# TCU_UCU_PCB_Rev2.net
KiCad netlist of a schematic drawn in EAGLE
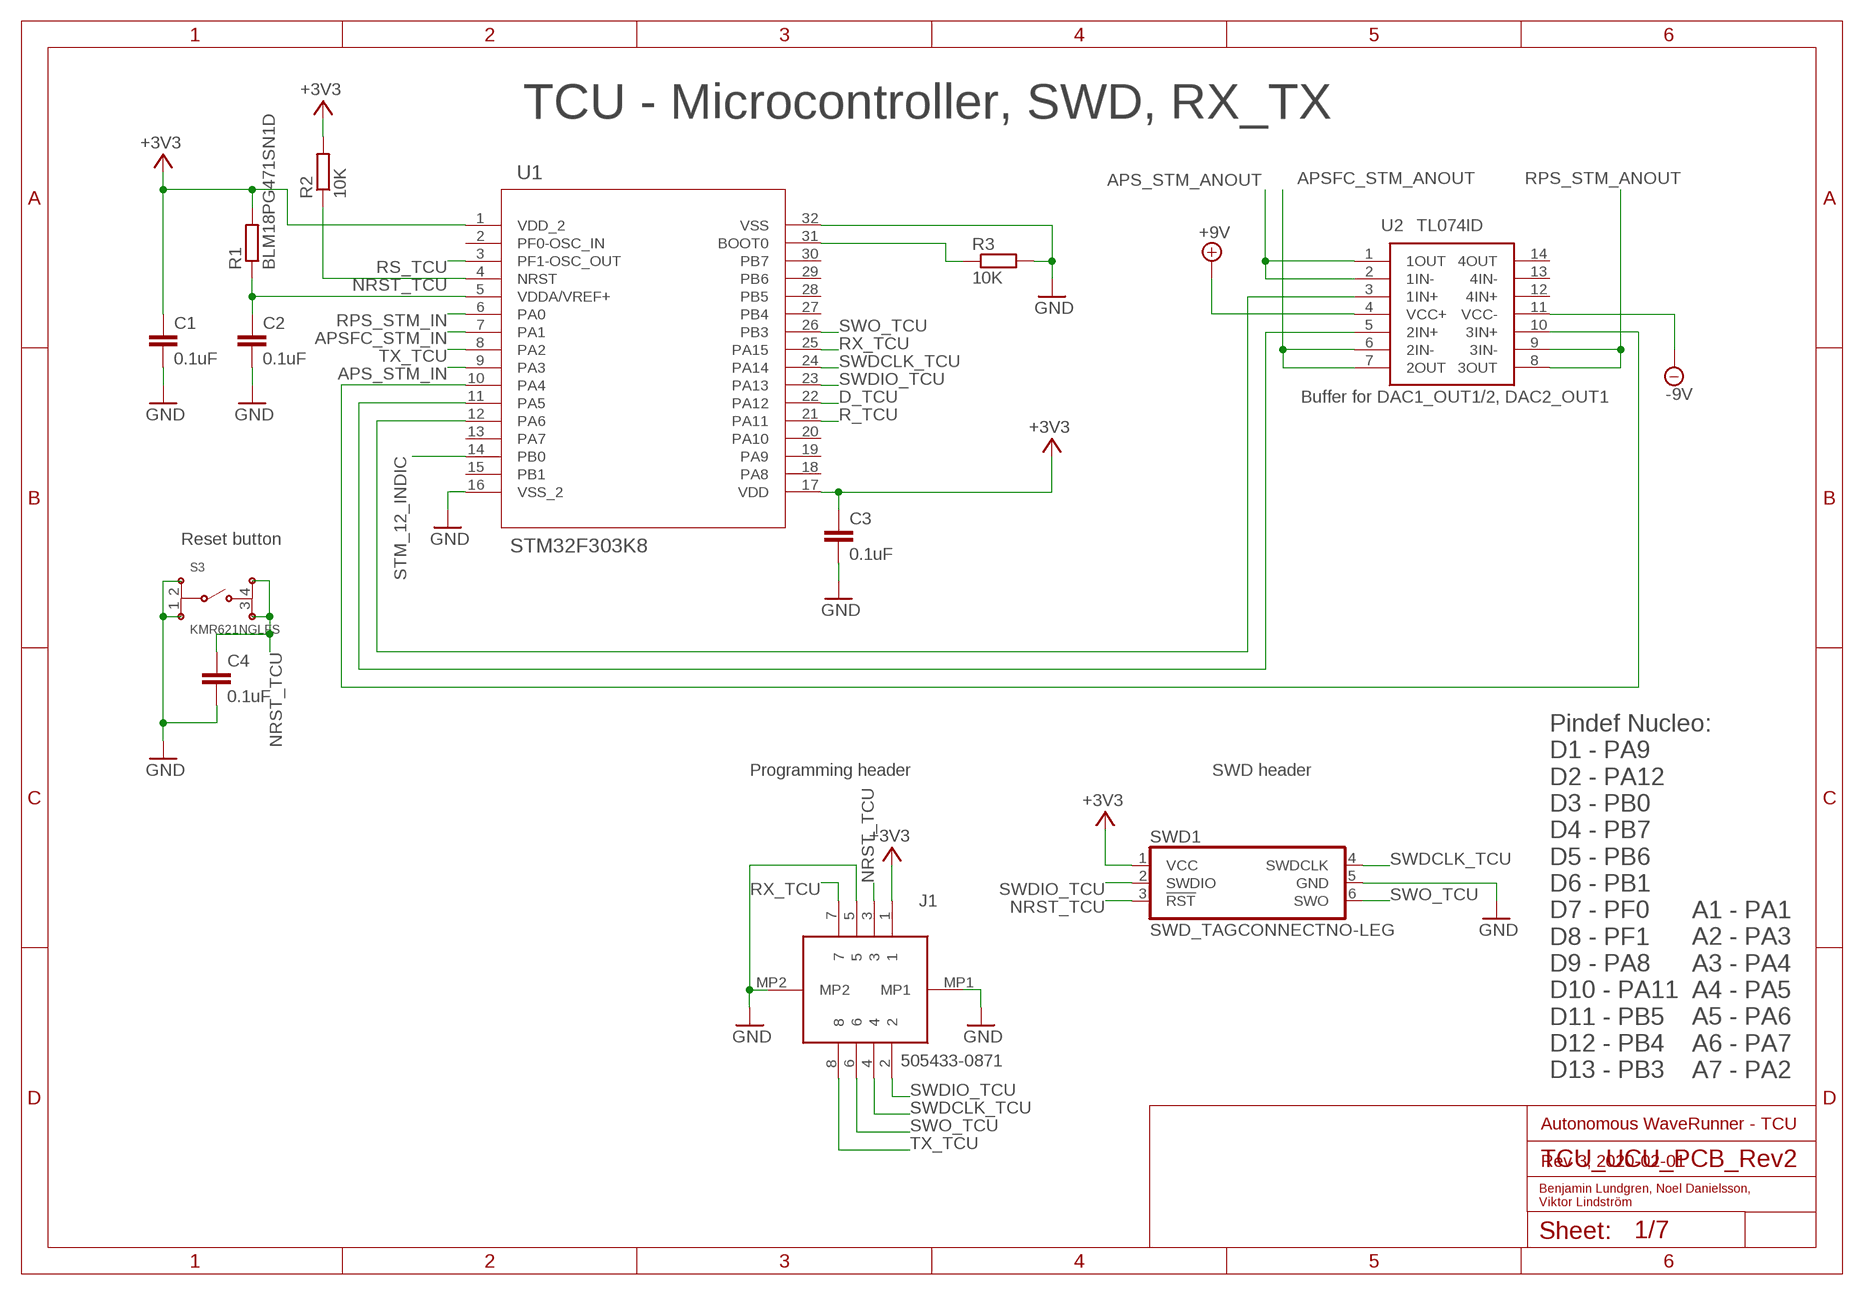
[diagram p0: schematic, sheet 1]
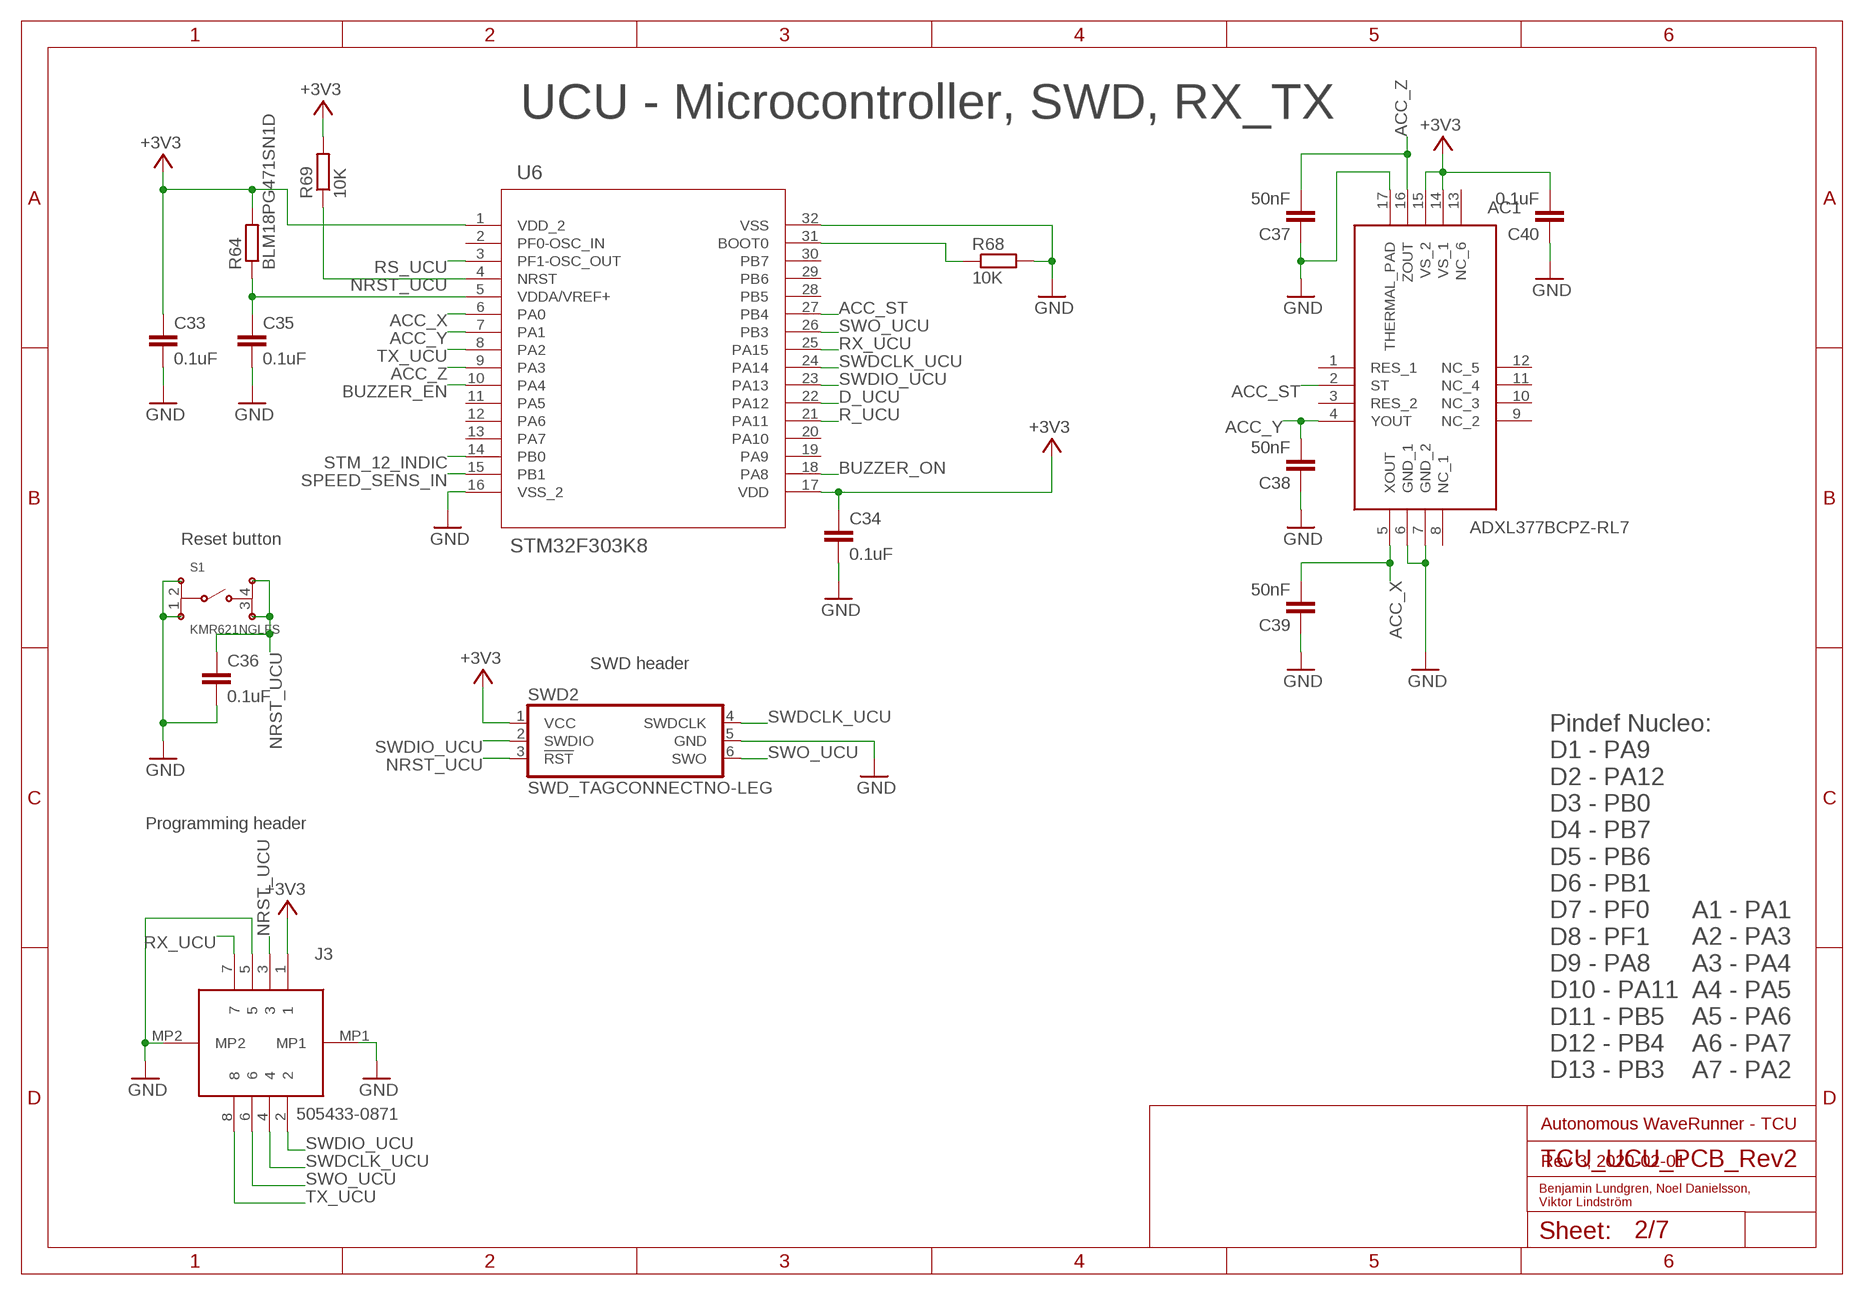
[diagram p1: schematic, sheet 2]
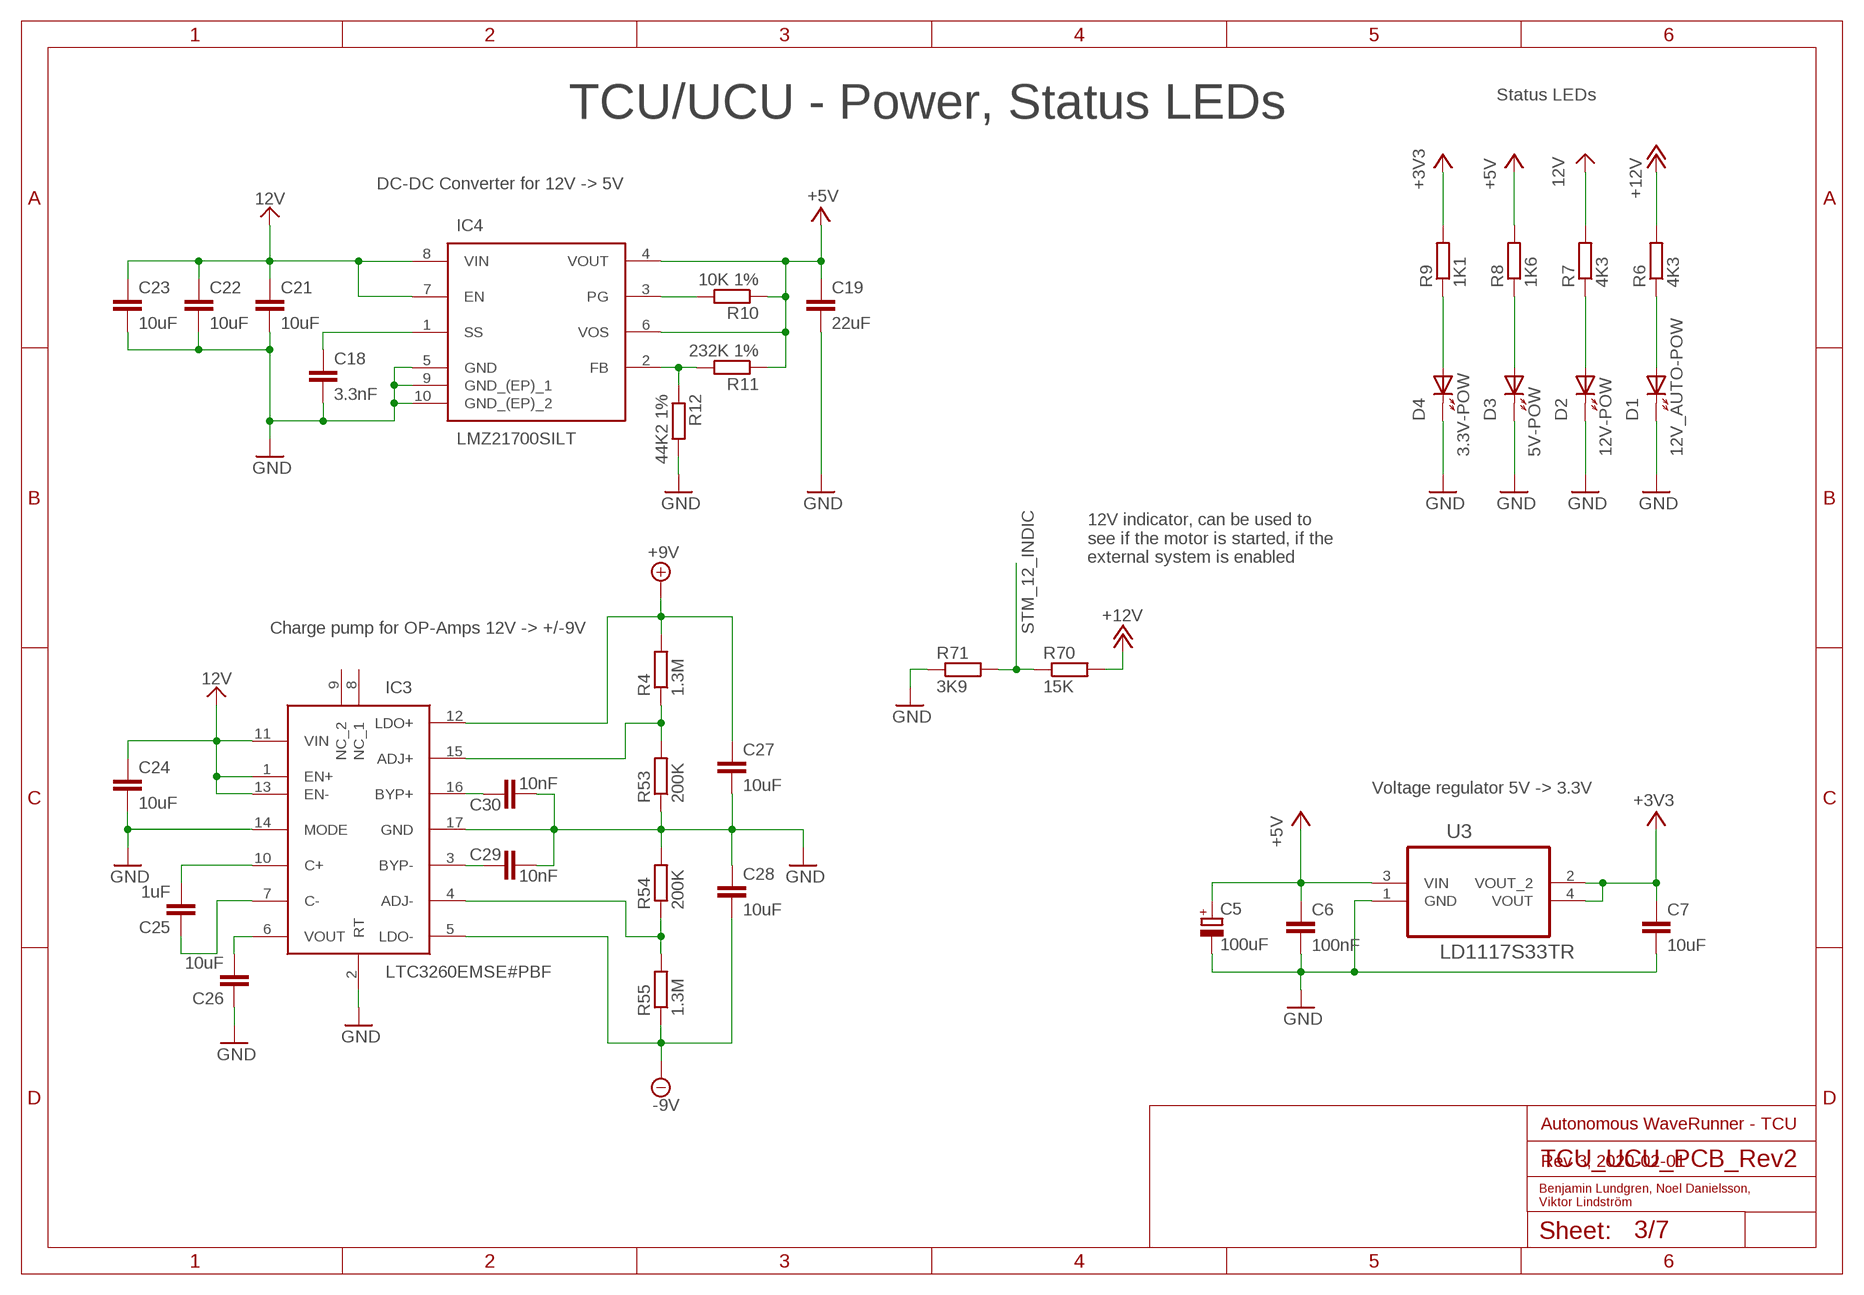
[diagram p2: schematic, sheet 3]
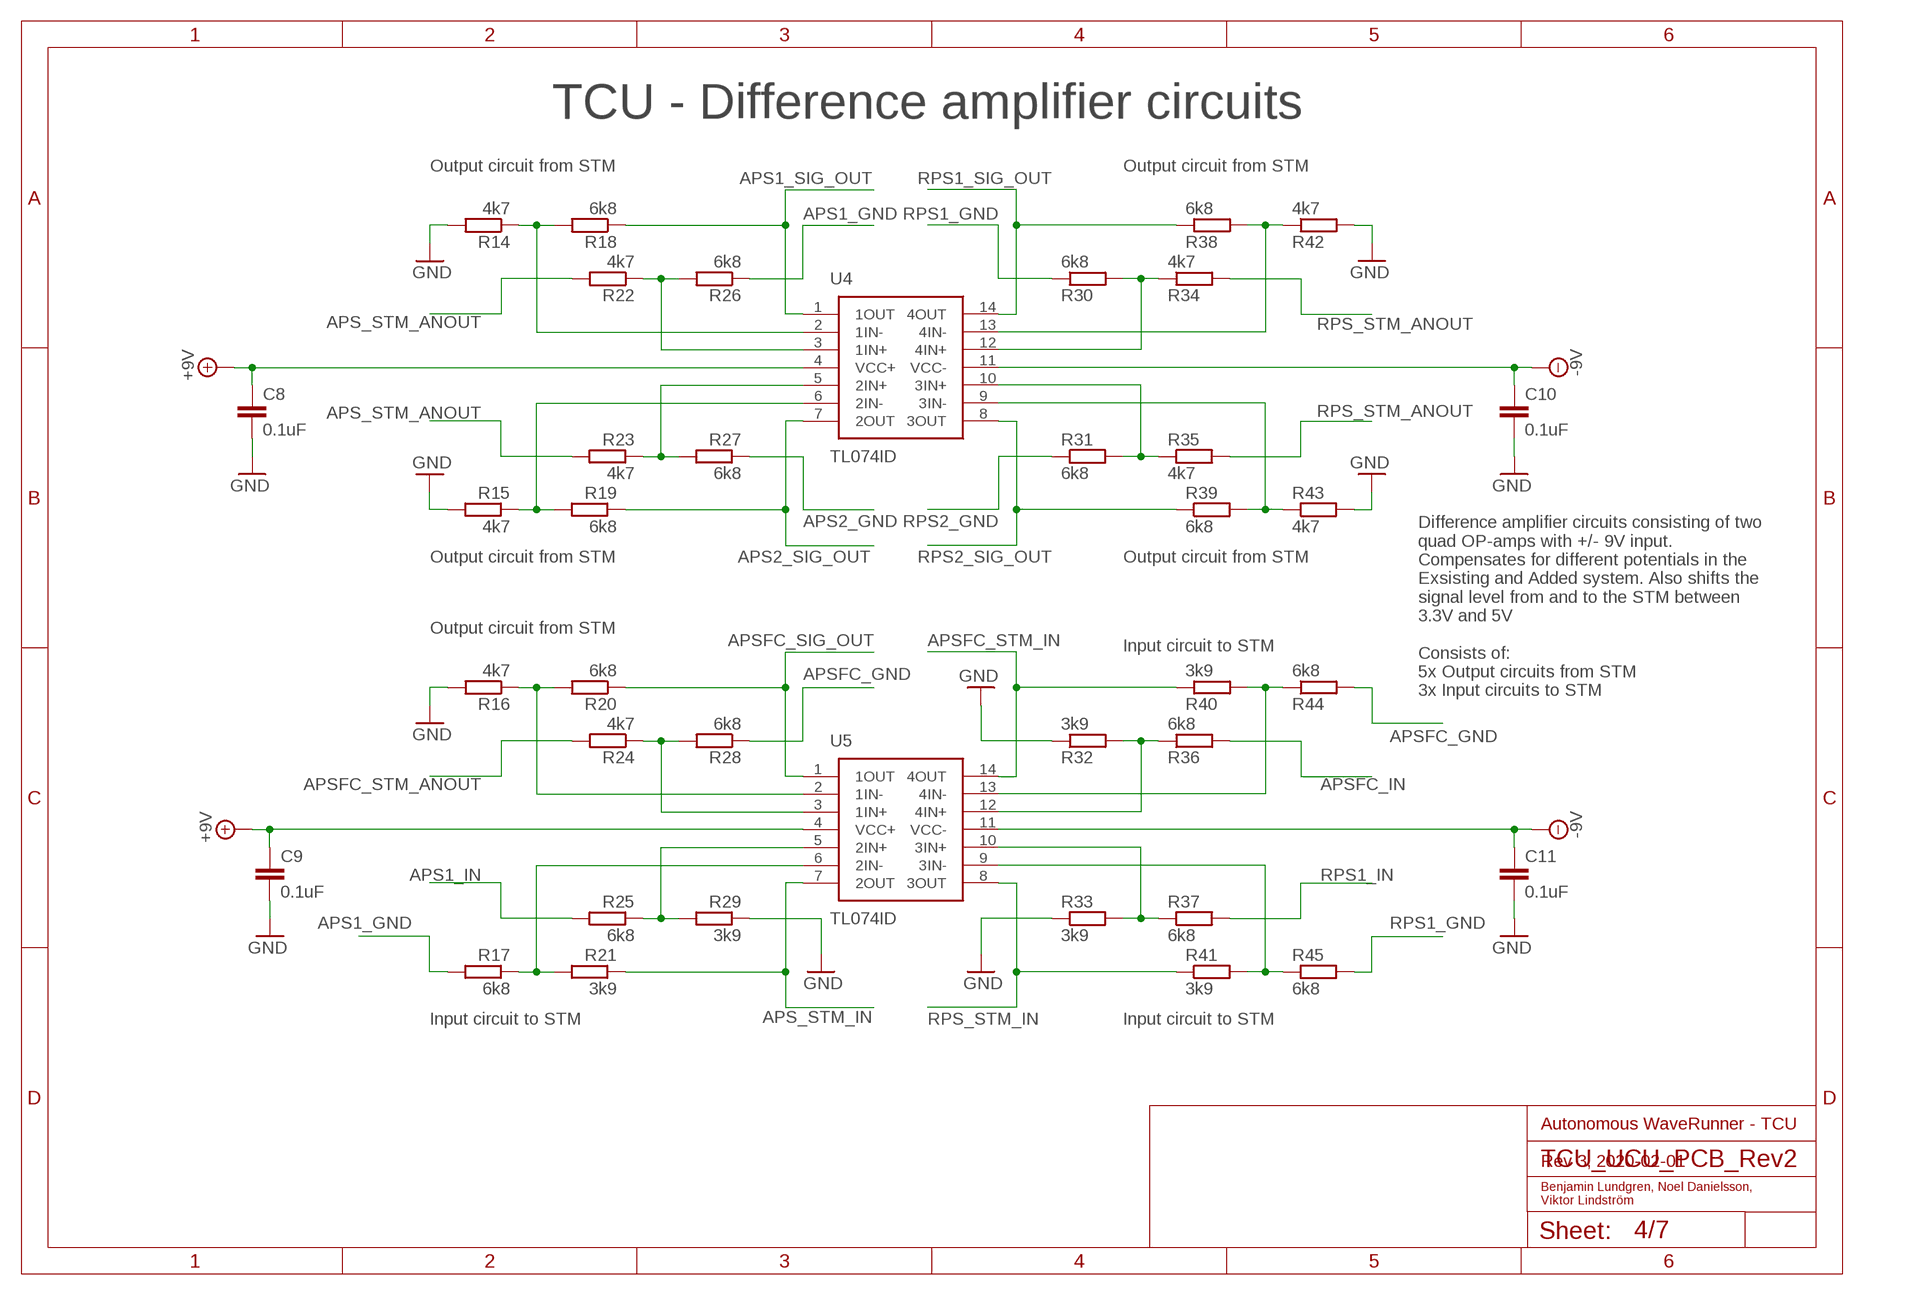
[diagram p3: schematic, sheet 4]
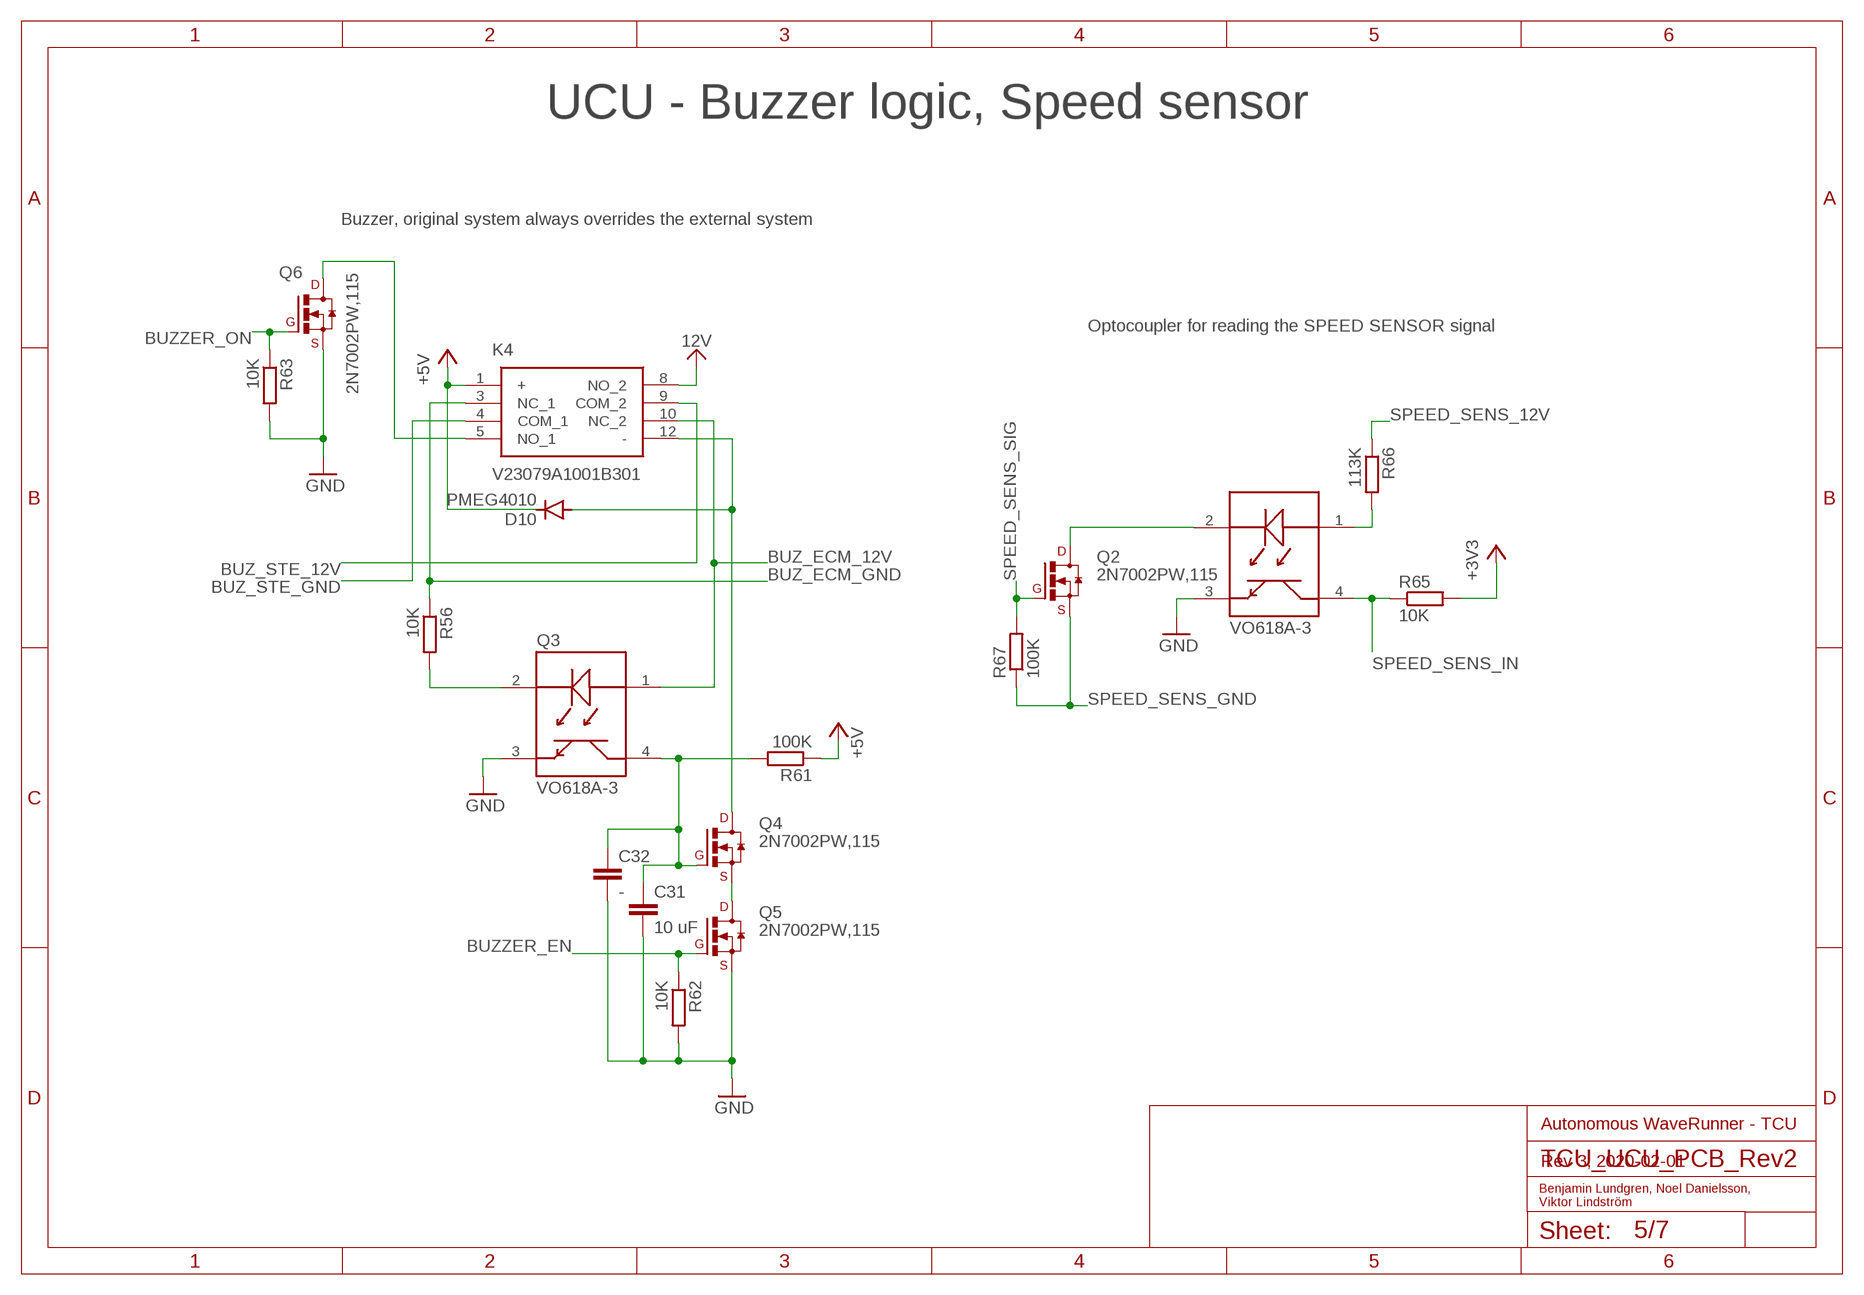
[diagram p4: schematic, sheet 5]
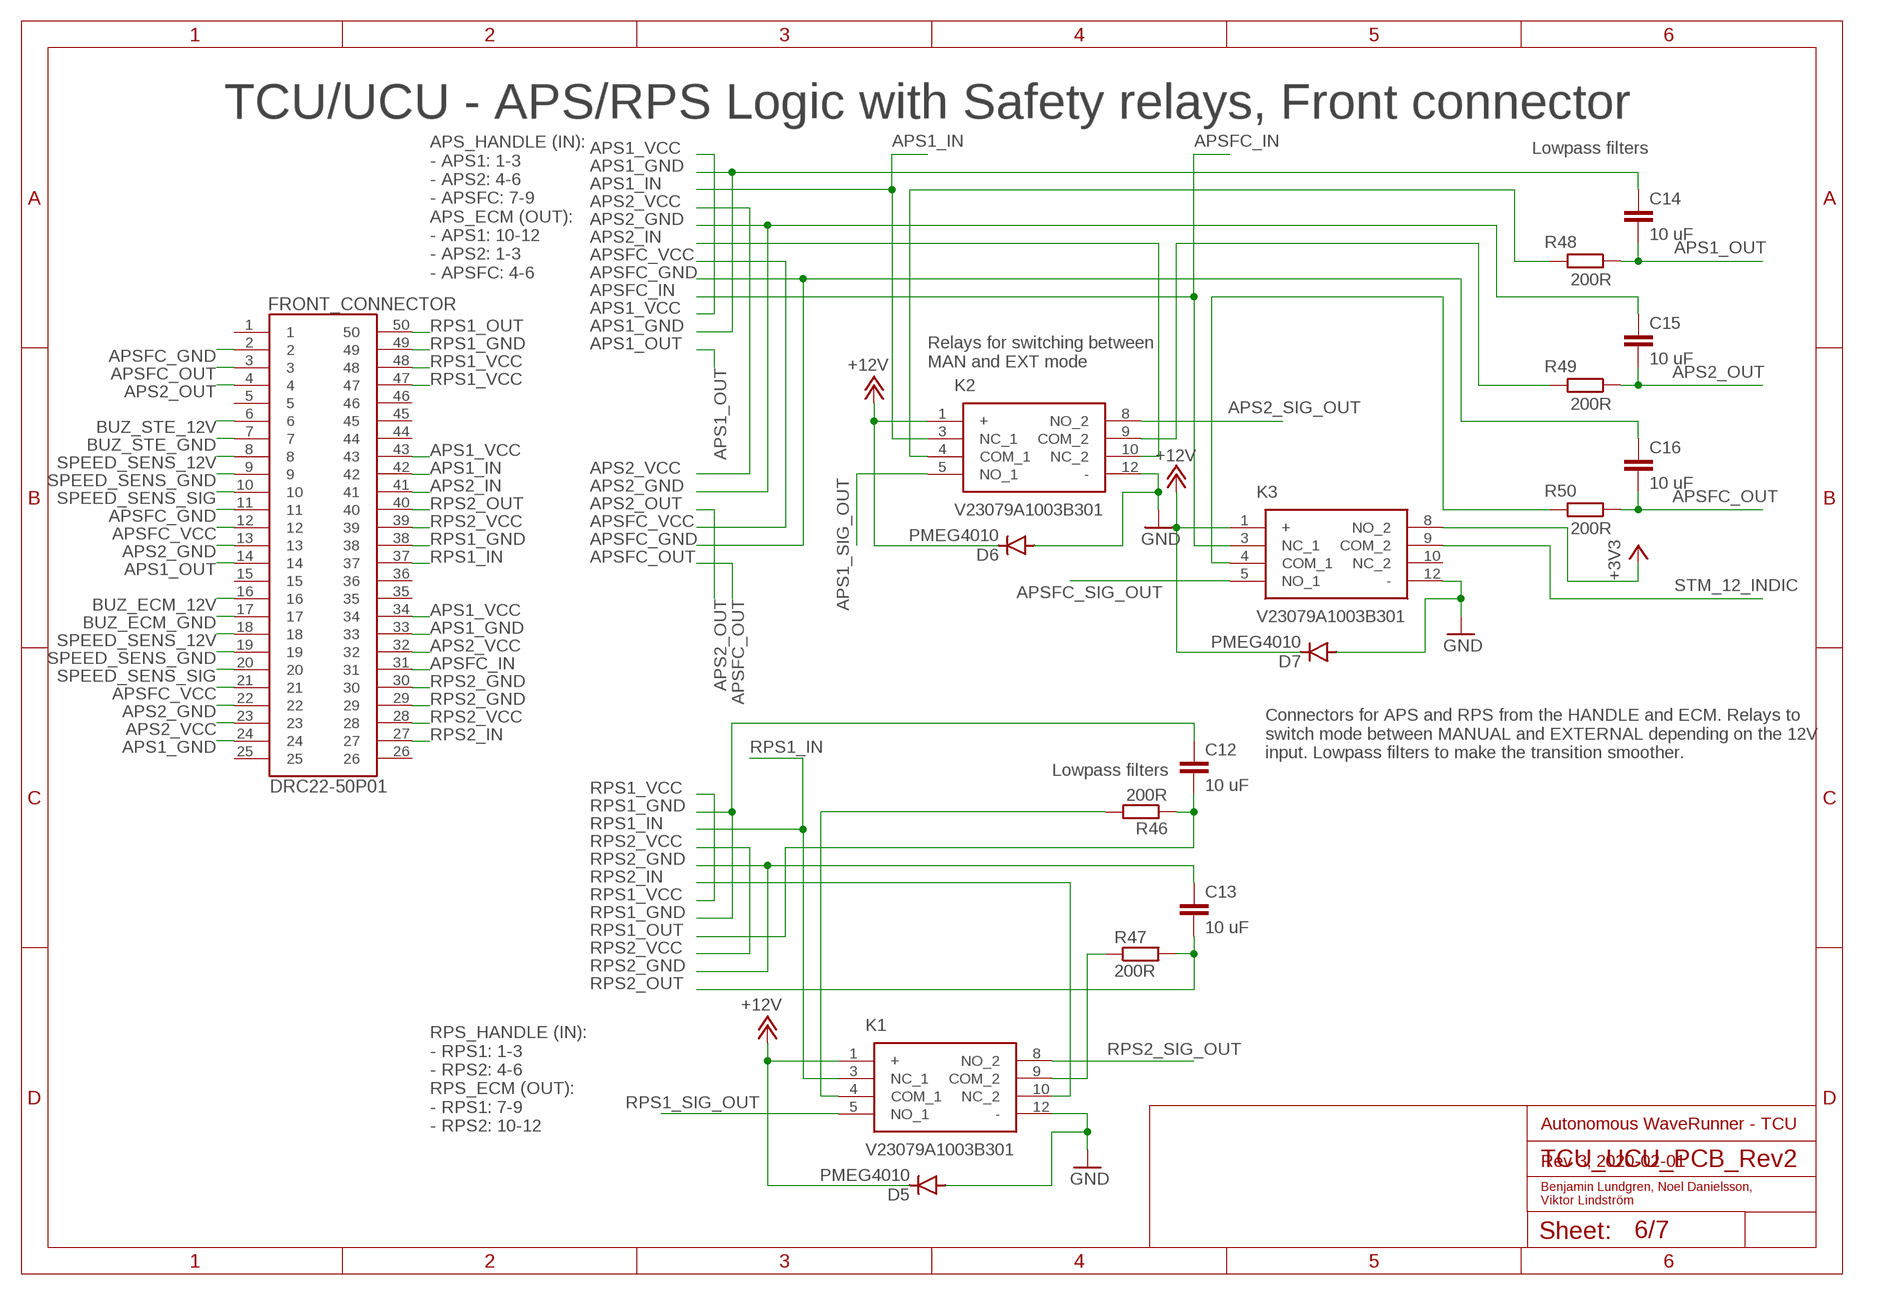
[diagram p5: schematic, sheet 6]
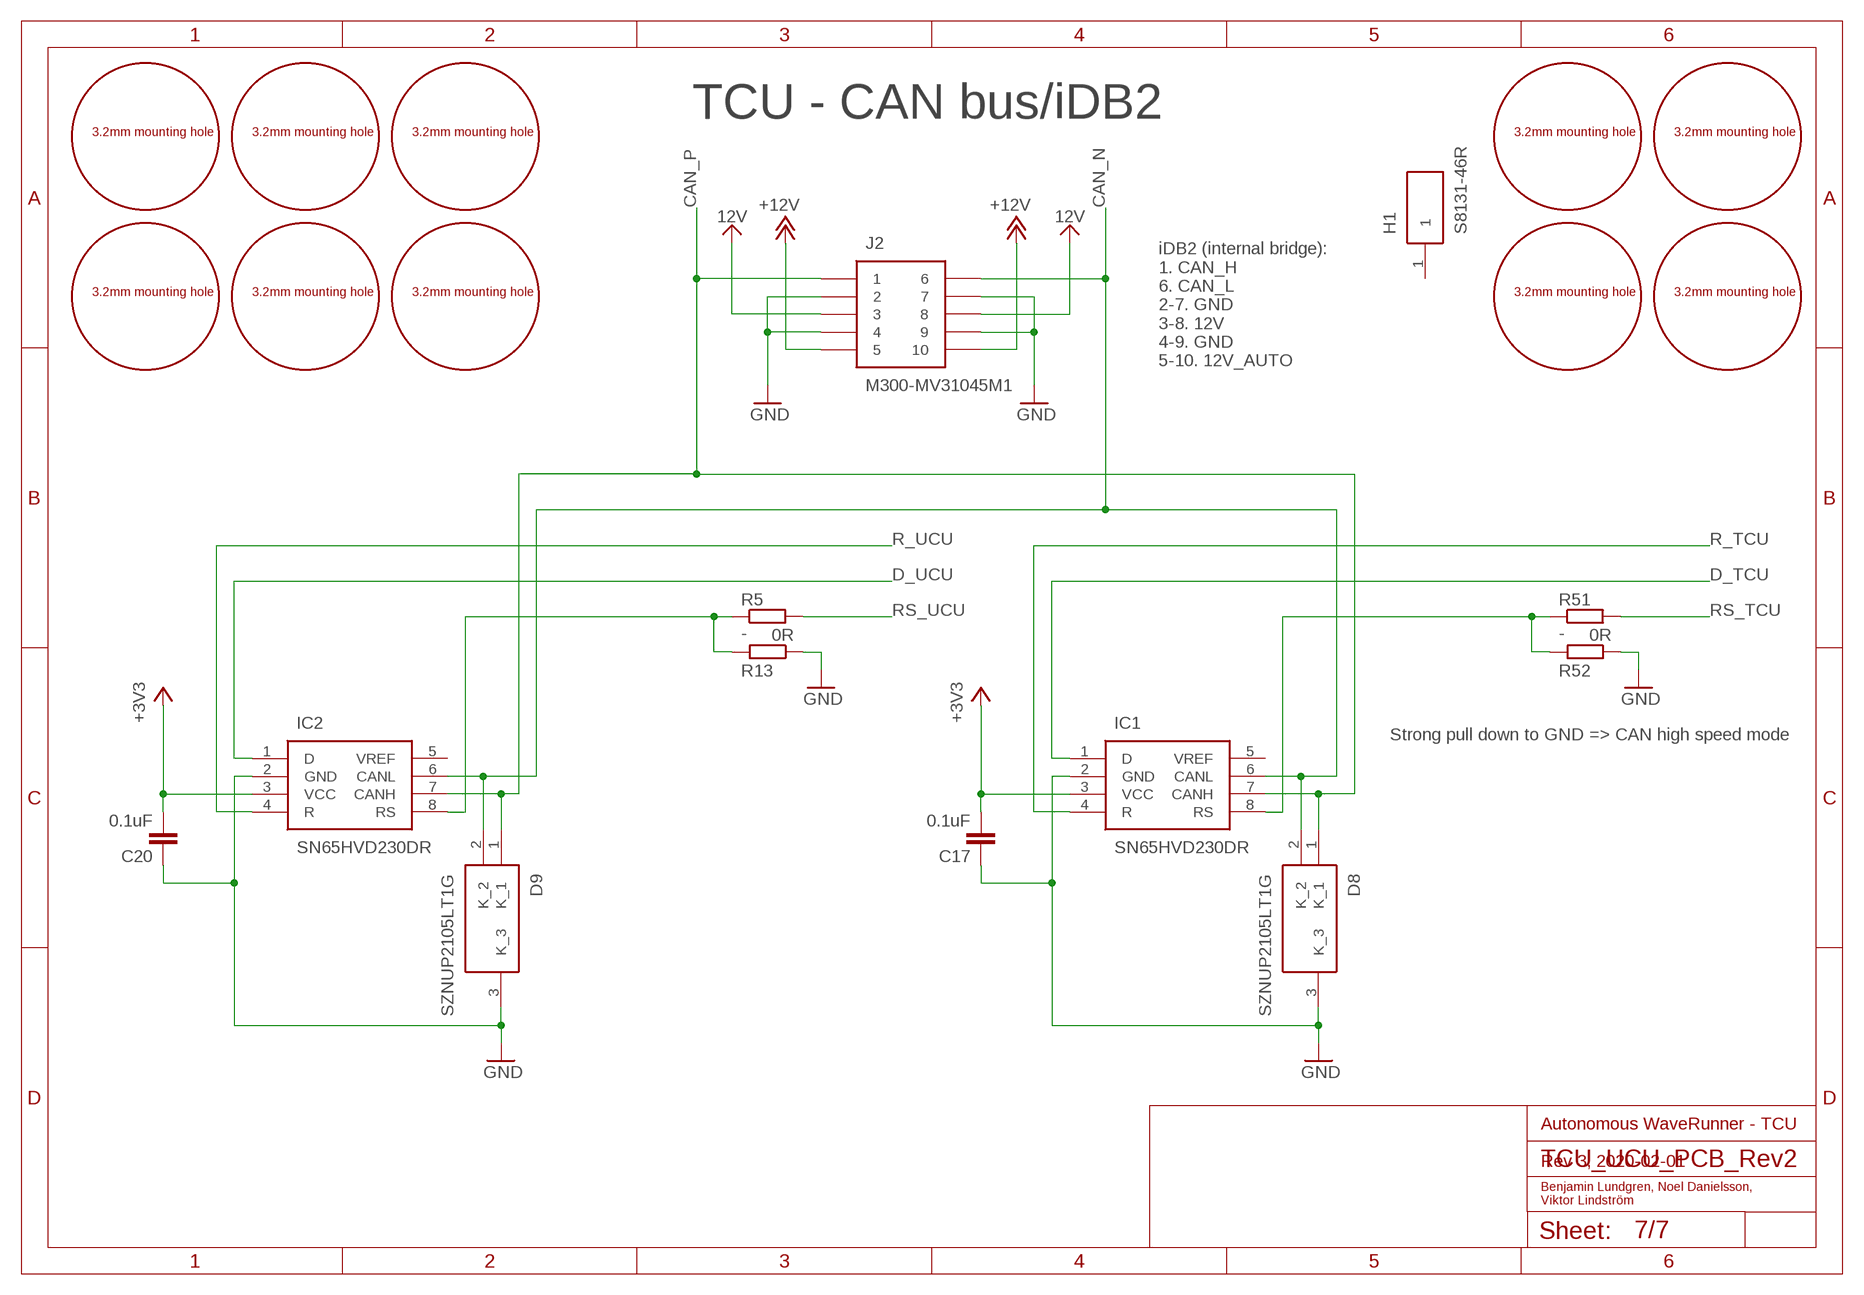
[diagram p6: schematic, sheet 7]

(export (version "E")
  (design (tool "Eeschema 10.0.6"))
  (components
    (comp (ref "AC1")
      (value "ADXL377BCPZ-RL7")
      (footprint "eagle-import:QFN50P300X300X150-17N")
      (fields (field (name "RS_PART_NUMBER") "1832638P"))
      (libsource (lib "eagle-import") (part "ADXL377BCPZ-RL7"))
    )
    (comp (ref "C33")
      (value "0.1uF")
      (footprint "eagle-import:C0603")
      (libsource (lib "eagle-import") (part "C0603"))
    )
    (comp (ref "C34")
      (value "0.1uF")
      (footprint "eagle-import:C0603")
      (libsource (lib "eagle-import") (part "C0603"))
    )
    (comp (ref "C35")
      (value "0.1uF")
      (footprint "eagle-import:C0603")
      (libsource (lib "eagle-import") (part "C0603"))
    )
    (comp (ref "C36")
      (value "0.1uF")
      (footprint "eagle-import:C0603")
      (libsource (lib "eagle-import") (part "C0603"))
    )
    (comp (ref "C37")
      (value "50nF")
      (footprint "eagle-import:C0603")
      (libsource (lib "eagle-import") (part "C0603"))
    )
    (comp (ref "C38")
      (value "50nF")
      (footprint "eagle-import:C0603")
      (libsource (lib "eagle-import") (part "C0603"))
    )
    (comp (ref "C39")
      (value "50nF")
      (footprint "eagle-import:C0603")
      (libsource (lib "eagle-import") (part "C0603"))
    )
    (comp (ref "C40")
      (value "0.1uF")
      (footprint "eagle-import:C0603")
      (libsource (lib "eagle-import") (part "C0603"))
    )
    (comp (ref "J3")
      (value "505433-0871")
      (footprint "eagle-import:5054330871")
      (fields (field (name "MANUFACTURER_PART_NUMBER") "5054330871"))
      (libsource (lib "eagle-import") (part "505433-0871"))
    )
    (comp (ref "R64")
      (value "BLM18PG471SN1D")
      (footprint "eagle-import:R0603")
      (libsource (lib "eagle-import") (part "R0603"))
    )
    (comp (ref "R68")
      (value "10K")
      (footprint "eagle-import:R0603")
      (libsource (lib "eagle-import") (part "R0603"))
    )
    (comp (ref "R69")
      (value "10K")
      (footprint "eagle-import:R0603")
      (libsource (lib "eagle-import") (part "R0603"))
    )
    (comp (ref "S1")
      (value "KMR621NGLFS")
      (footprint "eagle-import:KMR621NGLFS")
      (libsource (lib "eagle-import") (part "KMR621NGLFS"))
    )
    (comp (ref "SWD2")
      (value "SWD_TAGCONNECTNO-LEG")
      (footprint "eagle-import:TC2030-IDC-NL")
      (libsource (lib "eagle-import") (part "SWD_TAGCONNECTNO-LEG"))
    )
    (comp (ref "U6")
      (value "STM32F303K8")
      (footprint "eagle-import:LQFP-32")
      (fields (field (name "MANUFACTURER_PART_NUMBER") "stm32f303_334kxt"))
      (libsource (lib "eagle-import") (part "STM32F303K8"))
    )
    (comp (ref "C1")
      (value "0.1uF")
      (footprint "eagle-import:C0603")
      (libsource (lib "eagle-import") (part "C0603"))
    )
    (comp (ref "C2")
      (value "0.1uF")
      (footprint "eagle-import:C0603")
      (libsource (lib "eagle-import") (part "C0603"))
    )
    (comp (ref "C3")
      (value "0.1uF")
      (footprint "eagle-import:C0603")
      (libsource (lib "eagle-import") (part "C0603"))
    )
    (comp (ref "C4")
      (value "0.1uF")
      (footprint "eagle-import:C0603")
      (libsource (lib "eagle-import") (part "C0603"))
    )
    (comp (ref "J1")
      (value "505433-0871")
      (footprint "eagle-import:5054330871")
      (fields (field (name "MANUFACTURER_PART_NUMBER") "5054330871"))
      (libsource (lib "eagle-import") (part "505433-0871"))
    )
    (comp (ref "R1")
      (value "BLM18PG471SN1D")
      (footprint "eagle-import:R0603")
      (libsource (lib "eagle-import") (part "R0603"))
    )
    (comp (ref "R2")
      (value "10K")
      (footprint "eagle-import:R0603")
      (libsource (lib "eagle-import") (part "R0603"))
    )
    (comp (ref "R3")
      (value "10K")
      (footprint "eagle-import:R0603")
      (libsource (lib "eagle-import") (part "R0603"))
    )
    (comp (ref "S3")
      (value "KMR621NGLFS")
      (footprint "eagle-import:KMR621NGLFS")
      (libsource (lib "eagle-import") (part "KMR621NGLFS"))
    )
    (comp (ref "SWD1")
      (value "SWD_TAGCONNECTNO-LEG")
      (footprint "eagle-import:TC2030-IDC-NL")
      (libsource (lib "eagle-import") (part "SWD_TAGCONNECTNO-LEG"))
    )
    (comp (ref "U1")
      (value "STM32F303K8")
      (footprint "eagle-import:LQFP-32")
      (fields (field (name "MANUFACTURER_PART_NUMBER") "stm32f303_334kxt"))
      (libsource (lib "eagle-import") (part "STM32F303K8"))
    )
    (comp (ref "U2")
      (value "TL074ID")
      (footprint "eagle-import:SOIC127P600X175-14N")
      (fields (field (name "MOUSER_PART_NUMBER") "595-TL074ID"))
      (libsource (lib "eagle-import") (part "TL074ID"))
    )
    (comp (ref "C5")
      (value "100uF")
      (footprint "eagle-import:PANASONIC_C")
      (libsource (lib "eagle-import") (part "PANASONIC_C"))
    )
    (comp (ref "C6")
      (value "100nF")
      (footprint "eagle-import:C0603")
      (libsource (lib "eagle-import") (part "C0603"))
    )
    (comp (ref "C7")
      (value "10uF")
      (footprint "eagle-import:C0805")
      (libsource (lib "eagle-import") (part "C0805"))
    )
    (comp (ref "C18")
      (value "3.3nF")
      (footprint "eagle-import:C0603")
      (libsource (lib "eagle-import") (part "C0603"))
    )
    (comp (ref "C19")
      (value "22uF")
      (footprint "eagle-import:C0805")
      (libsource (lib "eagle-import") (part "C0805"))
    )
    (comp (ref "C21")
      (value "10uF")
      (footprint "eagle-import:C1206")
      (libsource (lib "eagle-import") (part "C1206"))
    )
    (comp (ref "C22")
      (value "10uF")
      (footprint "eagle-import:C1206")
      (libsource (lib "eagle-import") (part "C1206"))
    )
    (comp (ref "C23")
      (value "10uF")
      (footprint "eagle-import:C1206")
      (libsource (lib "eagle-import") (part "C1206"))
    )
    (comp (ref "C24")
      (value "10uF")
      (footprint "eagle-import:C1206")
      (libsource (lib "eagle-import") (part "C1206"))
    )
    (comp (ref "C25")
      (value "1uF")
      (footprint "eagle-import:C0805")
      (libsource (lib "eagle-import") (part "C0805"))
    )
    (comp (ref "C26")
      (value "10uF")
      (footprint "eagle-import:C1206")
      (libsource (lib "eagle-import") (part "C1206"))
    )
    (comp (ref "C27")
      (value "10uF")
      (footprint "eagle-import:C1206")
      (libsource (lib "eagle-import") (part "C1206"))
    )
    (comp (ref "C28")
      (value "10uF")
      (footprint "eagle-import:C1206")
      (libsource (lib "eagle-import") (part "C1206"))
    )
    (comp (ref "C29")
      (value "10nF")
      (footprint "eagle-import:C0603")
      (libsource (lib "eagle-import") (part "C0603"))
    )
    (comp (ref "C30")
      (value "10nF")
      (footprint "eagle-import:C0603")
      (libsource (lib "eagle-import") (part "C0603"))
    )
    (comp (ref "D1")
      (value "12V_AUTO-POW")
      (footprint "eagle-import:CHIP-LED0805")
      (libsource (lib "eagle-import") (part "CHIP-LED0805"))
    )
    (comp (ref "D2")
      (value "12V-POW")
      (footprint "eagle-import:CHIP-LED0805")
      (libsource (lib "eagle-import") (part "CHIP-LED0805"))
    )
    (comp (ref "D3")
      (value "5V-POW")
      (footprint "eagle-import:CHIP-LED0805")
      (libsource (lib "eagle-import") (part "CHIP-LED0805"))
    )
    (comp (ref "D4")
      (value "3.3V-POW")
      (footprint "eagle-import:CHIP-LED0805")
      (libsource (lib "eagle-import") (part "CHIP-LED0805"))
    )
    (comp (ref "IC3")
      (value "LTC3260EMSE#PBF")
      (footprint "eagle-import:SOP50P490X110-17N")
      (fields (field (name "RS_PART_NUMBER") "8516768P"))
      (libsource (lib "eagle-import") (part "LTC3260EMSE#PBF"))
    )
    (comp (ref "IC4")
      (value "LMZ21700SILT")
      (footprint "eagle-import:SIL0008E")
      (fields (field (name "RS_PART_NUMBER") "9009750P"))
      (libsource (lib "eagle-import") (part "LMZ21700SILT"))
    )
    (comp (ref "R4")
      (value "1.3M")
      (footprint "eagle-import:R0603")
      (libsource (lib "eagle-import") (part "R0603"))
    )
    (comp (ref "R6")
      (value "4K3")
      (footprint "eagle-import:R0603")
      (libsource (lib "eagle-import") (part "R0603"))
    )
    (comp (ref "R7")
      (value "4K3")
      (footprint "eagle-import:R0603")
      (libsource (lib "eagle-import") (part "R0603"))
    )
    (comp (ref "R8")
      (value "1K6")
      (footprint "eagle-import:R0603")
      (libsource (lib "eagle-import") (part "R0603"))
    )
    (comp (ref "R9")
      (value "1K1")
      (footprint "eagle-import:R0603")
      (libsource (lib "eagle-import") (part "R0603"))
    )
    (comp (ref "R10")
      (value "10K 1%")
      (footprint "eagle-import:R0603")
      (libsource (lib "eagle-import") (part "R0603"))
    )
    (comp (ref "R11")
      (value "232K 1%")
      (footprint "eagle-import:R0603")
      (libsource (lib "eagle-import") (part "R0603"))
    )
    (comp (ref "R12")
      (value "44K2 1%")
      (footprint "eagle-import:R0603")
      (libsource (lib "eagle-import") (part "R0603"))
    )
    (comp (ref "R53")
      (value "200K")
      (footprint "eagle-import:R0603")
      (libsource (lib "eagle-import") (part "R0603"))
    )
    (comp (ref "R54")
      (value "200K")
      (footprint "eagle-import:R0603")
      (libsource (lib "eagle-import") (part "R0603"))
    )
    (comp (ref "R55")
      (value "1.3M")
      (footprint "eagle-import:R0603")
      (libsource (lib "eagle-import") (part "R0603"))
    )
    (comp (ref "R70")
      (value "15K")
      (footprint "eagle-import:R0603")
      (libsource (lib "eagle-import") (part "R0603"))
    )
    (comp (ref "R71")
      (value "3K9")
      (footprint "eagle-import:R0603")
      (libsource (lib "eagle-import") (part "R0603"))
    )
    (comp (ref "U3")
      (value "LD1117S33TR")
      (footprint "eagle-import:SOT230P700X180-4N")
      (libsource (lib "eagle-import") (part "LD1117S33TR"))
    )
    (comp (ref "C8")
      (value "0.1uF")
      (footprint "eagle-import:C0805")
      (libsource (lib "eagle-import") (part "C0805"))
    )
    (comp (ref "C9")
      (value "0.1uF")
      (footprint "eagle-import:C0805")
      (libsource (lib "eagle-import") (part "C0805"))
    )
    (comp (ref "C10")
      (value "0.1uF")
      (footprint "eagle-import:C0805")
      (libsource (lib "eagle-import") (part "C0805"))
    )
    (comp (ref "C11")
      (value "0.1uF")
      (footprint "eagle-import:C0805")
      (libsource (lib "eagle-import") (part "C0805"))
    )
    (comp (ref "R14")
      (value "4k7")
      (footprint "eagle-import:R0603")
      (libsource (lib "eagle-import") (part "R0603"))
    )
    (comp (ref "R15")
      (value "4k7")
      (footprint "eagle-import:R0603")
      (libsource (lib "eagle-import") (part "R0603"))
    )
    (comp (ref "R16")
      (value "4k7")
      (footprint "eagle-import:R0603")
      (libsource (lib "eagle-import") (part "R0603"))
    )
    (comp (ref "R17")
      (value "6k8")
      (footprint "eagle-import:R0603")
      (libsource (lib "eagle-import") (part "R0603"))
    )
    (comp (ref "R18")
      (value "6k8")
      (footprint "eagle-import:R0603")
      (libsource (lib "eagle-import") (part "R0603"))
    )
    (comp (ref "R19")
      (value "6k8")
      (footprint "eagle-import:R0603")
      (libsource (lib "eagle-import") (part "R0603"))
    )
    (comp (ref "R20")
      (value "6k8")
      (footprint "eagle-import:R0603")
      (libsource (lib "eagle-import") (part "R0603"))
    )
    (comp (ref "R21")
      (value "3k9")
      (footprint "eagle-import:R0603")
      (libsource (lib "eagle-import") (part "R0603"))
    )
    (comp (ref "R22")
      (value "4k7")
      (footprint "eagle-import:R0603")
      (libsource (lib "eagle-import") (part "R0603"))
    )
    (comp (ref "R23")
      (value "4k7")
      (footprint "eagle-import:R0603")
      (libsource (lib "eagle-import") (part "R0603"))
    )
    (comp (ref "R24")
      (value "4k7")
      (footprint "eagle-import:R0603")
      (libsource (lib "eagle-import") (part "R0603"))
    )
    (comp (ref "R25")
      (value "6k8")
      (footprint "eagle-import:R0603")
      (libsource (lib "eagle-import") (part "R0603"))
    )
    (comp (ref "R26")
      (value "6k8")
      (footprint "eagle-import:R0603")
      (libsource (lib "eagle-import") (part "R0603"))
    )
    (comp (ref "R27")
      (value "6k8")
      (footprint "eagle-import:R0603")
      (libsource (lib "eagle-import") (part "R0603"))
    )
    (comp (ref "R28")
      (value "6k8")
      (footprint "eagle-import:R0603")
      (libsource (lib "eagle-import") (part "R0603"))
    )
    (comp (ref "R29")
      (value "3k9")
      (footprint "eagle-import:R0603")
      (libsource (lib "eagle-import") (part "R0603"))
    )
    (comp (ref "R30")
      (value "6k8")
      (footprint "eagle-import:R0603")
      (libsource (lib "eagle-import") (part "R0603"))
    )
    (comp (ref "R31")
      (value "6k8")
      (footprint "eagle-import:R0603")
      (libsource (lib "eagle-import") (part "R0603"))
    )
    (comp (ref "R32")
      (value "3k9")
      (footprint "eagle-import:R0603")
      (libsource (lib "eagle-import") (part "R0603"))
    )
    (comp (ref "R33")
      (value "3k9")
      (footprint "eagle-import:R0603")
      (libsource (lib "eagle-import") (part "R0603"))
    )
    (comp (ref "R34")
      (value "4k7")
      (footprint "eagle-import:R0603")
      (libsource (lib "eagle-import") (part "R0603"))
    )
    (comp (ref "R35")
      (value "4k7")
      (footprint "eagle-import:R0603")
      (libsource (lib "eagle-import") (part "R0603"))
    )
    (comp (ref "R36")
      (value "6k8")
      (footprint "eagle-import:R0603")
      (libsource (lib "eagle-import") (part "R0603"))
    )
    (comp (ref "R37")
      (value "6k8")
      (footprint "eagle-import:R0603")
      (libsource (lib "eagle-import") (part "R0603"))
    )
    (comp (ref "R38")
      (value "6k8")
      (footprint "eagle-import:R0603")
      (libsource (lib "eagle-import") (part "R0603"))
    )
    (comp (ref "R39")
      (value "6k8")
      (footprint "eagle-import:R0603")
      (libsource (lib "eagle-import") (part "R0603"))
    )
    (comp (ref "R40")
      (value "3k9")
      (footprint "eagle-import:R0603")
      (libsource (lib "eagle-import") (part "R0603"))
    )
    (comp (ref "R41")
      (value "3k9")
      (footprint "eagle-import:R0603")
      (libsource (lib "eagle-import") (part "R0603"))
    )
    (comp (ref "R42")
      (value "4k7")
      (footprint "eagle-import:R0603")
      (libsource (lib "eagle-import") (part "R0603"))
    )
    (comp (ref "R43")
      (value "4k7")
      (footprint "eagle-import:R0603")
      (libsource (lib "eagle-import") (part "R0603"))
    )
    (comp (ref "R44")
      (value "6k8")
      (footprint "eagle-import:R0603")
      (libsource (lib "eagle-import") (part "R0603"))
    )
    (comp (ref "R45")
      (value "6k8")
      (footprint "eagle-import:R0603")
      (libsource (lib "eagle-import") (part "R0603"))
    )
    (comp (ref "U4")
      (value "TL074ID")
      (footprint "eagle-import:SOIC127P600X175-14N")
      (fields (field (name "MOUSER_PART_NUMBER") "595-TL074ID"))
      (libsource (lib "eagle-import") (part "TL074ID"))
    )
    (comp (ref "U5")
      (value "TL074ID")
      (footprint "eagle-import:SOIC127P600X175-14N")
      (fields (field (name "MOUSER_PART_NUMBER") "595-TL074ID"))
      (libsource (lib "eagle-import") (part "TL074ID"))
    )
    (comp (ref "C12")
      (value "10 uF")
      (footprint "eagle-import:C0805")
      (libsource (lib "eagle-import") (part "C0805"))
    )
    (comp (ref "C13")
      (value "10 uF")
      (footprint "eagle-import:C0805")
      (libsource (lib "eagle-import") (part "C0805"))
    )
    (comp (ref "C14")
      (value "10 uF")
      (footprint "eagle-import:C0805")
      (libsource (lib "eagle-import") (part "C0805"))
    )
    (comp (ref "C15")
      (value "10 uF")
      (footprint "eagle-import:C0805")
      (libsource (lib "eagle-import") (part "C0805"))
    )
    (comp (ref "C16")
      (value "10 uF")
      (footprint "eagle-import:C0805")
      (libsource (lib "eagle-import") (part "C0805"))
    )
    (comp (ref "D5")
      (value "PMEG4010")
      (footprint "eagle-import:SOD123")
      (libsource (lib "eagle-import") (part "DIODE-SOD123"))
    )
    (comp (ref "D6")
      (value "PMEG4010")
      (footprint "eagle-import:SOD123")
      (libsource (lib "eagle-import") (part "DIODE-SOD123"))
    )
    (comp (ref "D7")
      (value "PMEG4010")
      (footprint "eagle-import:SOD123")
      (libsource (lib "eagle-import") (part "DIODE-SOD123"))
    )
    (comp (ref "FRONT_CONNECTOR")
      (value "DRC22-50P01")
      (footprint "eagle-import:TE_DRC22-50P01")
      (fields (field (name "MANUFACTURER") "TE Connectivity"))
      (libsource (lib "eagle-import") (part "DRC22-50P01"))
    )
    (comp (ref "K1")
      (value "V23079A1003B301")
      (footprint "eagle-import:413937885")
      (fields (field (name "MOUSER_PART_NUMBER") "655-V23079A1003B301"))
      (libsource (lib "eagle-import") (part "V23079A1003B301"))
    )
    (comp (ref "K2")
      (value "V23079A1003B301")
      (footprint "eagle-import:413937885")
      (fields (field (name "MOUSER_PART_NUMBER") "655-V23079A1003B301"))
      (libsource (lib "eagle-import") (part "V23079A1003B301"))
    )
    (comp (ref "K3")
      (value "V23079A1003B301")
      (footprint "eagle-import:413937885")
      (fields (field (name "MOUSER_PART_NUMBER") "655-V23079A1003B301"))
      (libsource (lib "eagle-import") (part "V23079A1003B301"))
    )
    (comp (ref "R46")
      (value "200R")
      (footprint "eagle-import:R0603")
      (libsource (lib "eagle-import") (part "R0603"))
    )
    (comp (ref "R47")
      (value "200R")
      (footprint "eagle-import:R0603")
      (libsource (lib "eagle-import") (part "R0603"))
    )
    (comp (ref "R48")
      (value "200R")
      (footprint "eagle-import:R0603")
      (libsource (lib "eagle-import") (part "R0603"))
    )
    (comp (ref "R49")
      (value "200R")
      (footprint "eagle-import:R0603")
      (libsource (lib "eagle-import") (part "R0603"))
    )
    (comp (ref "R50")
      (value "200R")
      (footprint "eagle-import:R0603")
      (libsource (lib "eagle-import") (part "R0603"))
    )
    (comp (ref "C17")
      (value "0.1uF")
      (footprint "eagle-import:C0603")
      (libsource (lib "eagle-import") (part "C0603"))
    )
    (comp (ref "C20")
      (value "0.1uF")
      (footprint "eagle-import:C0603")
      (libsource (lib "eagle-import") (part "C0603"))
    )
    (comp (ref "D8")
      (value "SZNUP2105LT1G")
      (footprint "eagle-import:SOT96P237X111-3N")
      (fields (field (name "MOUSER_PART_NUMBER") "863-SZNUP2105LT1G"))
      (libsource (lib "eagle-import") (part "SZNUP2105LT1G"))
    )
    (comp (ref "D9")
      (value "SZNUP2105LT1G")
      (footprint "eagle-import:SOT96P237X111-3N")
      (fields (field (name "MOUSER_PART_NUMBER") "863-SZNUP2105LT1G"))
      (libsource (lib "eagle-import") (part "SZNUP2105LT1G"))
    )
    (comp (ref "H1")
      (value "S8131-46R")
      (footprint "eagle-import:S813146R")
      (fields (field (name "RS_PART_NUMBER") "7884842P"))
      (libsource (lib "eagle-import") (part "S8131-46R"))
    )
    (comp (ref "IC1")
      (value "SN65HVD230DR")
      (footprint "eagle-import:SOT127P600X175-8N")
      (fields (field (name "MOUSER_PART_NUMBER") "595-SN65HVD230DR"))
      (libsource (lib "eagle-import") (part "SN65HVD230DR"))
    )
    (comp (ref "IC2")
      (value "SN65HVD230DR")
      (footprint "eagle-import:SOT127P600X175-8N")
      (fields (field (name "MOUSER_PART_NUMBER") "595-SN65HVD230DR"))
      (libsource (lib "eagle-import") (part "SN65HVD230DR"))
    )
    (comp (ref "J2")
      (value "M300-MV31045M1")
      (footprint "eagle-import:M300MV31045M1")
      (libsource (lib "eagle-import") (part "M300-MV31045M1"))
    )
    (comp (ref "R5")
      (value "-")
      (footprint "eagle-import:R0603")
      (libsource (lib "eagle-import") (part "R0603"))
    )
    (comp (ref "R13")
      (value "0R")
      (footprint "eagle-import:R0603")
      (libsource (lib "eagle-import") (part "R0603"))
    )
    (comp (ref "R51")
      (value "-")
      (footprint "eagle-import:R0603")
      (libsource (lib "eagle-import") (part "R0603"))
    )
    (comp (ref "R52")
      (value "0R")
      (footprint "eagle-import:R0603")
      (libsource (lib "eagle-import") (part "R0603"))
    )
    (comp (ref "U$1")
      (value "M3_MOUNTING_HOLE")
      (footprint "eagle-import:M3_MOUNTING_HOLE")
      (libsource (lib "eagle-import") (part "M3_MOUNTING_HOLE"))
    )
    (comp (ref "U$2")
      (value "M3_MOUNTING_HOLE")
      (footprint "eagle-import:M3_MOUNTING_HOLE")
      (libsource (lib "eagle-import") (part "M3_MOUNTING_HOLE"))
    )
    (comp (ref "U$3")
      (value "M3_MOUNTING_HOLE")
      (footprint "eagle-import:M3_MOUNTING_HOLE")
      (libsource (lib "eagle-import") (part "M3_MOUNTING_HOLE"))
    )
    (comp (ref "U$4")
      (value "M3_MOUNTING_HOLE")
      (footprint "eagle-import:M3_MOUNTING_HOLE")
      (libsource (lib "eagle-import") (part "M3_MOUNTING_HOLE"))
    )
    (comp (ref "U$5")
      (value "M3_MOUNTING_HOLE")
      (footprint "eagle-import:M3_MOUNTING_HOLE")
      (libsource (lib "eagle-import") (part "M3_MOUNTING_HOLE"))
    )
    (comp (ref "U$6")
      (value "M3_MOUNTING_HOLE")
      (footprint "eagle-import:M3_MOUNTING_HOLE")
      (libsource (lib "eagle-import") (part "M3_MOUNTING_HOLE"))
    )
    (comp (ref "U$7")
      (value "M3_MOUNTING_HOLE")
      (footprint "eagle-import:M3_MOUNTING_HOLE")
      (libsource (lib "eagle-import") (part "M3_MOUNTING_HOLE"))
    )
    (comp (ref "U$8")
      (value "M3_MOUNTING_HOLE")
      (footprint "eagle-import:M3_MOUNTING_HOLE")
      (libsource (lib "eagle-import") (part "M3_MOUNTING_HOLE"))
    )
    (comp (ref "U$9")
      (value "M3_MOUNTING_HOLE")
      (footprint "eagle-import:M3_MOUNTING_HOLE")
      (libsource (lib "eagle-import") (part "M3_MOUNTING_HOLE"))
    )
    (comp (ref "U$10")
      (value "M3_MOUNTING_HOLE")
      (footprint "eagle-import:M3_MOUNTING_HOLE")
      (libsource (lib "eagle-import") (part "M3_MOUNTING_HOLE"))
    )
    (comp (ref "C31")
      (value "10 uF")
      (footprint "eagle-import:C0805")
      (libsource (lib "eagle-import") (part "C0805"))
    )
    (comp (ref "C32")
      (value "-")
      (footprint "eagle-import:C1206")
      (libsource (lib "eagle-import") (part "C1206"))
    )
    (comp (ref "D10")
      (value "PMEG4010")
      (footprint "eagle-import:SOD123")
      (libsource (lib "eagle-import") (part "DIODE-SOD123"))
    )
    (comp (ref "K4")
      (value "V23079A1001B301")
      (footprint "eagle-import:413937885")
      (fields
        (field (name "MANUFACTURER_PART_NUMBER") "V23079A1003B301")
        (field (name "MOUSER_PART_NUMBER") "655-V23079A1003B301")
      )
      (libsource (lib "eagle-import") (part "V23079A1001B301"))
    )
    (comp (ref "Q2")
      (value "2N7002PW,115")
      (footprint "eagle-import:SOT323")
      (libsource (lib "eagle-import") (part "2N7002PW,115"))
    )
    (comp (ref "Q3")
      (value "VO618A-3")
      (footprint "eagle-import:DIL04-400")
      (libsource (lib "eagle-import") (part "VO618A-3"))
    )
    (comp (ref "Q4")
      (value "2N7002PW,115")
      (footprint "eagle-import:SOT323")
      (libsource (lib "eagle-import") (part "2N7002PW,115"))
    )
    (comp (ref "Q5")
      (value "2N7002PW,115")
      (footprint "eagle-import:SOT323")
      (libsource (lib "eagle-import") (part "2N7002PW,115"))
    )
    (comp (ref "Q6")
      (value "2N7002PW,115")
      (footprint "eagle-import:SOT323")
      (libsource (lib "eagle-import") (part "2N7002PW,115"))
    )
    (comp (ref "Q7")
      (value "VO618A-3")
      (footprint "eagle-import:DIL04-400")
      (libsource (lib "eagle-import") (part "VO618A-3"))
    )
    (comp (ref "R56")
      (value "10K")
      (footprint "eagle-import:R0603")
      (libsource (lib "eagle-import") (part "R0603"))
    )
    (comp (ref "R61")
      (value "100K")
      (footprint "eagle-import:R0603")
      (libsource (lib "eagle-import") (part "R0603"))
    )
    (comp (ref "R62")
      (value "10K")
      (footprint "eagle-import:R0603")
      (libsource (lib "eagle-import") (part "R0603"))
    )
    (comp (ref "R63")
      (value "10K")
      (footprint "eagle-import:R0603")
      (libsource (lib "eagle-import") (part "R0603"))
    )
    (comp (ref "R65")
      (value "10K")
      (footprint "eagle-import:R0603")
      (libsource (lib "eagle-import") (part "R0603"))
    )
    (comp (ref "R66")
      (value "113K")
      (footprint "eagle-import:R0603")
      (libsource (lib "eagle-import") (part "R0603"))
    )
    (comp (ref "R67")
      (value "100K")
      (footprint "eagle-import:R0603")
      (libsource (lib "eagle-import") (part "R0603"))
    )
  )
  (nets
    (net (code "1") (name "+3V3") (class "Default")
      (node (ref "AC1") (pin "14") (pinfunction "VS_1_14") (pintype "bidirectional"))
      (node (ref "AC1") (pin "15") (pinfunction "VS_2_15") (pintype "bidirectional"))
      (node (ref "C1") (pin "1") (pinfunction "1_1") (pintype "passive"))
      (node (ref "C17") (pin "2") (pinfunction "2_2") (pintype "passive"))
      (node (ref "C20") (pin "2") (pinfunction "2_2") (pintype "passive"))
      (node (ref "C3") (pin "1") (pinfunction "1_1") (pintype "passive"))
      (node (ref "C33") (pin "1") (pinfunction "1_1") (pintype "passive"))
      (node (ref "C34") (pin "1") (pinfunction "1_1") (pintype "passive"))
      (node (ref "C40") (pin "2") (pinfunction "2_2") (pintype "passive"))
      (node (ref "C7") (pin "1") (pinfunction "1_1") (pintype "passive"))
      (node (ref "IC1") (pin "3") (pinfunction "VCC_3") (pintype "bidirectional"))
      (node (ref "IC2") (pin "3") (pinfunction "VCC_3") (pintype "bidirectional"))
      (node (ref "J1") (pin "1") (pinfunction "1_1") (pintype "bidirectional"))
      (node (ref "J3") (pin "1") (pinfunction "1_1") (pintype "bidirectional"))
      (node (ref "K3") (pin "8") (pinfunction "NO_2_8") (pintype "bidirectional"))
      (node (ref "R1") (pin "2") (pinfunction "2_2") (pintype "passive"))
      (node (ref "R2") (pin "2") (pinfunction "2_2") (pintype "passive"))
      (node (ref "R64") (pin "2") (pinfunction "2_2") (pintype "passive"))
      (node (ref "R65") (pin "2") (pinfunction "2_2") (pintype "passive"))
      (node (ref "R69") (pin "2") (pinfunction "2_2") (pintype "passive"))
      (node (ref "R9") (pin "2") (pinfunction "2_2") (pintype "passive"))
      (node (ref "SWD1") (pin "1") (pinfunction "VCC_1") (pintype "passive"))
      (node (ref "SWD2") (pin "1") (pinfunction "VCC_1") (pintype "passive"))
      (node (ref "U1") (pin "1") (pinfunction "VDD_2_1") (pintype "power_in"))
      (node (ref "U1") (pin "17") (pinfunction "VDD_17") (pintype "power_in"))
      (node (ref "U3") (pin "2") (pinfunction "VOUT_2_2") (pintype "output"))
      (node (ref "U3") (pin "4") (pinfunction "VOUT_4") (pintype "output"))
      (node (ref "U6") (pin "1") (pinfunction "VDD_2_1") (pintype "power_in"))
      (node (ref "U6") (pin "17") (pinfunction "VDD_17") (pintype "power_in"))
    )
    (net (code "2") (name "+5V") (class "Default")
      (node (ref "C19") (pin "1") (pinfunction "1_1") (pintype "passive"))
      (node (ref "C5") (pin "+") (pinfunction "+_+") (pintype "passive"))
      (node (ref "C6") (pin "1") (pinfunction "1_1") (pintype "passive"))
      (node (ref "D10") (pin "C") (pinfunction "C_C") (pintype "passive"))
      (node (ref "IC4") (pin "4") (pinfunction "VOUT_4") (pintype "output"))
      (node (ref "IC4") (pin "6") (pinfunction "VOS_6") (pintype "bidirectional"))
      (node (ref "K4") (pin "1") (pinfunction "+_1") (pintype "bidirectional"))
      (node (ref "R10") (pin "1") (pinfunction "1_1") (pintype "passive"))
      (node (ref "R11") (pin "1") (pinfunction "1_1") (pintype "passive"))
      (node (ref "R61") (pin "1") (pinfunction "1_1") (pintype "passive"))
      (node (ref "R8") (pin "2") (pinfunction "2_2") (pintype "passive"))
      (node (ref "U3") (pin "3") (pinfunction "VIN_3") (pintype "input"))
    )
    (net (code "3") (name "+9V") (class "Default")
      (node (ref "C27") (pin "1") (pinfunction "1_1") (pintype "passive"))
      (node (ref "C8") (pin "1") (pinfunction "1_1") (pintype "passive"))
      (node (ref "C9") (pin "1") (pinfunction "1_1") (pintype "passive"))
      (node (ref "IC3") (pin "12") (pinfunction "LDO+_12") (pintype "output"))
      (node (ref "R4") (pin "2") (pinfunction "2_2") (pintype "passive"))
      (node (ref "U2") (pin "4") (pinfunction "VCC+_4") (pintype "power_in"))
      (node (ref "U4") (pin "4") (pinfunction "VCC+_4") (pintype "power_in"))
      (node (ref "U5") (pin "4") (pinfunction "VCC+_4") (pintype "power_in"))
    )
    (net (code "4") (name "+12V") (class "Default")
      (node (ref "D5") (pin "C") (pinfunction "C_C") (pintype "passive"))
      (node (ref "D6") (pin "C") (pinfunction "C_C") (pintype "passive"))
      (node (ref "D7") (pin "C") (pinfunction "C_C") (pintype "passive"))
      (node (ref "J2") (pin "10") (pinfunction "10_10") (pintype "bidirectional"))
      (node (ref "J2") (pin "5") (pinfunction "5_5") (pintype "bidirectional"))
      (node (ref "K1") (pin "1") (pinfunction "+_1") (pintype "bidirectional"))
      (node (ref "K2") (pin "1") (pinfunction "+_1") (pintype "bidirectional"))
      (node (ref "K3") (pin "1") (pinfunction "+_1") (pintype "bidirectional"))
      (node (ref "R6") (pin "2") (pinfunction "2_2") (pintype "passive"))
      (node (ref "R70") (pin "2") (pinfunction "2_2") (pintype "passive"))
    )
    (net (code "5") (name "-9V") (class "Default")
      (node (ref "C10") (pin "1") (pinfunction "1_1") (pintype "passive"))
      (node (ref "C11") (pin "1") (pinfunction "1_1") (pintype "passive"))
      (node (ref "C28") (pin "2") (pinfunction "2_2") (pintype "passive"))
      (node (ref "IC3") (pin "5") (pinfunction "LDO-_5") (pintype "output"))
      (node (ref "R55") (pin "1") (pinfunction "1_1") (pintype "passive"))
      (node (ref "U2") (pin "11") (pinfunction "VCC-_11") (pintype "power_in"))
      (node (ref "U4") (pin "11") (pinfunction "VCC-_11") (pintype "power_in"))
      (node (ref "U5") (pin "11") (pinfunction "VCC-_11") (pintype "power_in"))
    )
    (net (code "6") (name "12V") (class "Default")
      (node (ref "C21") (pin "1") (pinfunction "1_1") (pintype "passive"))
      (node (ref "C22") (pin "1") (pinfunction "1_1") (pintype "passive"))
      (node (ref "C23") (pin "1") (pinfunction "1_1") (pintype "passive"))
      (node (ref "C24") (pin "1") (pinfunction "1_1") (pintype "passive"))
      (node (ref "IC3") (pin "1") (pinfunction "EN+_1") (pintype "input"))
      (node (ref "IC3") (pin "11") (pinfunction "VIN_11") (pintype "power_in"))
      (node (ref "IC3") (pin "13") (pinfunction "EN-_13") (pintype "input"))
      (node (ref "IC4") (pin "7") (pinfunction "EN_7") (pintype "bidirectional"))
      (node (ref "IC4") (pin "8") (pinfunction "VIN_8") (pintype "input"))
      (node (ref "J2") (pin "3") (pinfunction "3_3") (pintype "bidirectional"))
      (node (ref "J2") (pin "8") (pinfunction "8_8") (pintype "bidirectional"))
      (node (ref "K4") (pin "8") (pinfunction "NO_2_8") (pintype "bidirectional"))
      (node (ref "R7") (pin "2") (pinfunction "2_2") (pintype "passive"))
    )
    (net (code "7") (name "ACC_ST") (class "Default")
      (node (ref "AC1") (pin "2") (pinfunction "ST_2") (pintype "bidirectional"))
      (node (ref "U6") (pin "27") (pinfunction "PB4_27") (pintype "bidirectional"))
    )
    (net (code "8") (name "ACC_X") (class "Default")
      (node (ref "AC1") (pin "5") (pinfunction "XOUT_5") (pintype "bidirectional"))
      (node (ref "C39") (pin "2") (pinfunction "2_2") (pintype "passive"))
      (node (ref "U6") (pin "6") (pinfunction "PA0_6") (pintype "bidirectional"))
    )
    (net (code "9") (name "ACC_Y") (class "Default")
      (node (ref "AC1") (pin "4") (pinfunction "YOUT_4") (pintype "bidirectional"))
      (node (ref "C38") (pin "2") (pinfunction "2_2") (pintype "passive"))
      (node (ref "U6") (pin "7") (pinfunction "PA1_7") (pintype "bidirectional"))
    )
    (net (code "10") (name "ACC_Z") (class "Default")
      (node (ref "AC1") (pin "16") (pinfunction "ZOUT_16") (pintype "bidirectional"))
      (node (ref "C37") (pin "2") (pinfunction "2_2") (pintype "passive"))
      (node (ref "U6") (pin "9") (pinfunction "PA3_9") (pintype "bidirectional"))
    )
    (net (code "11") (name "APS1_GND") (class "Default")
      (node (ref "C14") (pin "1") (pinfunction "1_1") (pintype "passive"))
      (node (ref "FRONT_CONNECTOR") (pin "24") (pinfunction "24_24") (pintype "passive"))
      (node (ref "FRONT_CONNECTOR") (pin "33") (pinfunction "33_33") (pintype "passive"))
      (node (ref "R17") (pin "2") (pinfunction "2_2") (pintype "passive"))
      (node (ref "R26") (pin "1") (pinfunction "1_1") (pintype "passive"))
    )
    (net (code "12") (name "APS1_IN") (class "Default")
      (node (ref "FRONT_CONNECTOR") (pin "42") (pinfunction "42_42") (pintype "passive"))
      (node (ref "K2") (pin "3") (pinfunction "NC_1_3") (pintype "bidirectional"))
      (node (ref "R25") (pin "2") (pinfunction "2_2") (pintype "passive"))
    )
    (net (code "13") (name "APS1_OUT") (class "Default")
      (node (ref "C14") (pin "2") (pinfunction "2_2") (pintype "passive"))
      (node (ref "FRONT_CONNECTOR") (pin "14") (pinfunction "14_14") (pintype "passive"))
      (node (ref "R48") (pin "1") (pinfunction "1_1") (pintype "passive"))
    )
    (net (code "14") (name "APS1_SIG_OUT") (class "Default")
      (node (ref "K2") (pin "5") (pinfunction "NO_1_5") (pintype "bidirectional"))
      (node (ref "R18") (pin "1") (pinfunction "1_1") (pintype "passive"))
      (node (ref "U4") (pin "1") (pinfunction "1OUT_1") (pintype "output"))
    )
    (net (code "15") (name "APS1_VCC") (class "Default")
      (node (ref "FRONT_CONNECTOR") (pin "34") (pinfunction "34_34") (pintype "passive"))
      (node (ref "FRONT_CONNECTOR") (pin "43") (pinfunction "43_43") (pintype "passive"))
    )
    (net (code "16") (name "APS2_GND") (class "Default")
      (node (ref "C15") (pin "1") (pinfunction "1_1") (pintype "passive"))
      (node (ref "FRONT_CONNECTOR") (pin "13") (pinfunction "13_13") (pintype "passive"))
      (node (ref "FRONT_CONNECTOR") (pin "22") (pinfunction "22_22") (pintype "passive"))
      (node (ref "R27") (pin "1") (pinfunction "1_1") (pintype "passive"))
    )
    (net (code "17") (name "APS2_IN") (class "Default")
      (node (ref "FRONT_CONNECTOR") (pin "41") (pinfunction "41_41") (pintype "passive"))
      (node (ref "K2") (pin "10") (pinfunction "NC_2_10") (pintype "bidirectional"))
    )
    (net (code "18") (name "APS2_OUT") (class "Default")
      (node (ref "C15") (pin "2") (pinfunction "2_2") (pintype "passive"))
      (node (ref "FRONT_CONNECTOR") (pin "4") (pinfunction "4_4") (pintype "passive"))
      (node (ref "R49") (pin "1") (pinfunction "1_1") (pintype "passive"))
    )
    (net (code "19") (name "APS2_SIG_OUT") (class "Default")
      (node (ref "K2") (pin "8") (pinfunction "NO_2_8") (pintype "bidirectional"))
      (node (ref "R19") (pin "1") (pinfunction "1_1") (pintype "passive"))
      (node (ref "U4") (pin "7") (pinfunction "2OUT_7") (pintype "output"))
    )
    (net (code "20") (name "APS2_VCC") (class "Default")
      (node (ref "FRONT_CONNECTOR") (pin "23") (pinfunction "23_23") (pintype "passive"))
      (node (ref "FRONT_CONNECTOR") (pin "32") (pinfunction "32_32") (pintype "passive"))
    )
    (net (code "21") (name "APSFC_GND") (class "Default")
      (node (ref "C16") (pin "1") (pinfunction "1_1") (pintype "passive"))
      (node (ref "FRONT_CONNECTOR") (pin "11") (pinfunction "11_11") (pintype "passive"))
      (node (ref "FRONT_CONNECTOR") (pin "2") (pinfunction "2_2") (pintype "passive"))
      (node (ref "R28") (pin "1") (pinfunction "1_1") (pintype "passive"))
      (node (ref "R44") (pin "2") (pinfunction "2_2") (pintype "passive"))
    )
    (net (code "22") (name "APSFC_IN") (class "Default")
      (node (ref "FRONT_CONNECTOR") (pin "31") (pinfunction "31_31") (pintype "passive"))
      (node (ref "K3") (pin "3") (pinfunction "NC_1_3") (pintype "bidirectional"))
      (node (ref "R36") (pin "2") (pinfunction "2_2") (pintype "passive"))
    )
    (net (code "23") (name "APSFC_OUT") (class "Default")
      (node (ref "C16") (pin "2") (pinfunction "2_2") (pintype "passive"))
      (node (ref "FRONT_CONNECTOR") (pin "3") (pinfunction "3_3") (pintype "passive"))
      (node (ref "R50") (pin "1") (pinfunction "1_1") (pintype "passive"))
    )
    (net (code "24") (name "APSFC_SIG_OUT") (class "Default")
      (node (ref "K3") (pin "5") (pinfunction "NO_1_5") (pintype "bidirectional"))
      (node (ref "R20") (pin "1") (pinfunction "1_1") (pintype "passive"))
      (node (ref "U5") (pin "1") (pinfunction "1OUT_1") (pintype "output"))
    )
    (net (code "25") (name "APSFC_STM_ANOUT") (class "Default")
      (node (ref "R24") (pin "2") (pinfunction "2_2") (pintype "passive"))
      (node (ref "U2") (pin "6") (pinfunction "2IN-_6") (pintype "input"))
      (node (ref "U2") (pin "7") (pinfunction "2OUT_7") (pintype "output"))
    )
    (net (code "26") (name "APSFC_STM_IN") (class "Default")
      (node (ref "R40") (pin "1") (pinfunction "1_1") (pintype "passive"))
      (node (ref "U1") (pin "7") (pinfunction "PA1_7") (pintype "bidirectional"))
      (node (ref "U5") (pin "14") (pinfunction "4OUT_14") (pintype "output"))
    )
    (net (code "27") (name "APSFC_VCC") (class "Default")
      (node (ref "FRONT_CONNECTOR") (pin "12") (pinfunction "12_12") (pintype "passive"))
      (node (ref "FRONT_CONNECTOR") (pin "21") (pinfunction "21_21") (pintype "passive"))
    )
    (net (code "28") (name "APS_STM_ANOUT") (class "Default")
      (node (ref "R22") (pin "2") (pinfunction "2_2") (pintype "passive"))
      (node (ref "R23") (pin "2") (pinfunction "2_2") (pintype "passive"))
      (node (ref "U2") (pin "1") (pinfunction "1OUT_1") (pintype "output"))
      (node (ref "U2") (pin "2") (pinfunction "1IN-_2") (pintype "input"))
    )
    (net (code "29") (name "APS_STM_IN") (class "Default")
      (node (ref "R21") (pin "1") (pinfunction "1_1") (pintype "passive"))
      (node (ref "U1") (pin "9") (pinfunction "PA3_9") (pintype "bidirectional"))
      (node (ref "U5") (pin "7") (pinfunction "2OUT_7") (pintype "output"))
    )
    (net (code "30") (name "BUZZER_EN") (class "Default")
      (node (ref "Q5") (pin "1") (pinfunction "G_1") (pintype "passive"))
      (node (ref "R62") (pin "1") (pinfunction "1_1") (pintype "passive"))
      (node (ref "U6") (pin "10") (pinfunction "PA4_10") (pintype "bidirectional"))
    )
    (net (code "31") (name "BUZZER_ON") (class "Default")
      (node (ref "Q6") (pin "1") (pinfunction "G_1") (pintype "passive"))
      (node (ref "R63") (pin "1") (pinfunction "1_1") (pintype "passive"))
      (node (ref "U6") (pin "18") (pinfunction "PA8_18") (pintype "bidirectional"))
    )
    (net (code "32") (name "BUZ_ECM_12V") (class "Default")
      (node (ref "FRONT_CONNECTOR") (pin "16") (pinfunction "16_16") (pintype "passive"))
      (node (ref "K4") (pin "10") (pinfunction "NC_2_10") (pintype "bidirectional"))
      (node (ref "Q3") (pin "1") (pinfunction "1A_1") (pintype "bidirectional"))
    )
    (net (code "33") (name "BUZ_ECM_GND") (class "Default")
      (node (ref "FRONT_CONNECTOR") (pin "17") (pinfunction "17_17") (pintype "passive"))
      (node (ref "K4") (pin "3") (pinfunction "NC_1_3") (pintype "bidirectional"))
      (node (ref "R56") (pin "1") (pinfunction "1_1") (pintype "passive"))
    )
    (net (code "34") (name "BUZ_STE_12V") (class "Default")
      (node (ref "FRONT_CONNECTOR") (pin "6") (pinfunction "6_6") (pintype "passive"))
      (node (ref "K4") (pin "9") (pinfunction "COM_2_9") (pintype "bidirectional"))
    )
    (net (code "35") (name "BUZ_STE_GND") (class "Default")
      (node (ref "FRONT_CONNECTOR") (pin "7") (pinfunction "7_7") (pintype "passive"))
      (node (ref "K4") (pin "4") (pinfunction "COM_1_4") (pintype "bidirectional"))
    )
    (net (code "36") (name "CAN_N") (class "Default")
      (node (ref "D8") (pin "2") (pinfunction "K_2_2") (pintype "bidirectional"))
      (node (ref "D9") (pin "2") (pinfunction "K_2_2") (pintype "bidirectional"))
      (node (ref "IC1") (pin "6") (pinfunction "CANL_6") (pintype "bidirectional"))
      (node (ref "IC2") (pin "6") (pinfunction "CANL_6") (pintype "bidirectional"))
      (node (ref "J2") (pin "6") (pinfunction "6_6") (pintype "bidirectional"))
    )
    (net (code "37") (name "CAN_P") (class "Default")
      (node (ref "D8") (pin "1") (pinfunction "K_1_1") (pintype "bidirectional"))
      (node (ref "D9") (pin "1") (pinfunction "K_1_1") (pintype "bidirectional"))
      (node (ref "IC1") (pin "7") (pinfunction "CANH_7") (pintype "bidirectional"))
      (node (ref "IC2") (pin "7") (pinfunction "CANH_7") (pintype "bidirectional"))
      (node (ref "J2") (pin "1") (pinfunction "1_1") (pintype "bidirectional"))
    )
    (net (code "38") (name "D_TCU") (class "Default")
      (node (ref "IC1") (pin "1") (pinfunction "D_1") (pintype "bidirectional"))
      (node (ref "U1") (pin "22") (pinfunction "PA12_22") (pintype "bidirectional"))
    )
    (net (code "39") (name "D_UCU") (class "Default")
      (node (ref "IC2") (pin "1") (pinfunction "D_1") (pintype "bidirectional"))
      (node (ref "U6") (pin "22") (pinfunction "PA12_22") (pintype "bidirectional"))
    )
    (net (code "40") (name "GND") (class "Default")
      (node (ref "AC1") (pin "17") (pinfunction "THERMAL_PAD_17") (pintype "bidirectional"))
      (node (ref "AC1") (pin "6") (pinfunction "GND_1_6") (pintype "bidirectional"))
      (node (ref "AC1") (pin "7") (pinfunction "GND_2_7") (pintype "bidirectional"))
      (node (ref "C1") (pin "2") (pinfunction "2_2") (pintype "passive"))
      (node (ref "C10") (pin "2") (pinfunction "2_2") (pintype "passive"))
      (node (ref "C11") (pin "2") (pinfunction "2_2") (pintype "passive"))
      (node (ref "C17") (pin "1") (pinfunction "1_1") (pintype "passive"))
      (node (ref "C18") (pin "2") (pinfunction "2_2") (pintype "passive"))
      (node (ref "C19") (pin "2") (pinfunction "2_2") (pintype "passive"))
      (node (ref "C2") (pin "2") (pinfunction "2_2") (pintype "passive"))
      (node (ref "C20") (pin "1") (pinfunction "1_1") (pintype "passive"))
      (node (ref "C21") (pin "2") (pinfunction "2_2") (pintype "passive"))
      (node (ref "C22") (pin "2") (pinfunction "2_2") (pintype "passive"))
      (node (ref "C23") (pin "2") (pinfunction "2_2") (pintype "passive"))
      (node (ref "C24") (pin "2") (pinfunction "2_2") (pintype "passive"))
      (node (ref "C26") (pin "1") (pinfunction "1_1") (pintype "passive"))
      (node (ref "C27") (pin "2") (pinfunction "2_2") (pintype "passive"))
      (node (ref "C28") (pin "1") (pinfunction "1_1") (pintype "passive"))
      (node (ref "C29") (pin "2") (pinfunction "2_2") (pintype "passive"))
      (node (ref "C3") (pin "2") (pinfunction "2_2") (pintype "passive"))
      (node (ref "C30") (pin "2") (pinfunction "2_2") (pintype "passive"))
      (node (ref "C31") (pin "2") (pinfunction "2_2") (pintype "passive"))
      (node (ref "C32") (pin "2") (pinfunction "2_2") (pintype "passive"))
      (node (ref "C33") (pin "2") (pinfunction "2_2") (pintype "passive"))
      (node (ref "C34") (pin "2") (pinfunction "2_2") (pintype "passive"))
      (node (ref "C35") (pin "2") (pinfunction "2_2") (pintype "passive"))
      (node (ref "C36") (pin "2") (pinfunction "2_2") (pintype "passive"))
      (node (ref "C37") (pin "1") (pinfunction "1_1") (pintype "passive"))
      (node (ref "C38") (pin "1") (pinfunction "1_1") (pintype "passive"))
      (node (ref "C39") (pin "1") (pinfunction "1_1") (pintype "passive"))
      (node (ref "C4") (pin "2") (pinfunction "2_2") (pintype "passive"))
      (node (ref "C40") (pin "1") (pinfunction "1_1") (pintype "passive"))
      (node (ref "C5") (pin "-") (pinfunction "-_-") (pintype "passive"))
      (node (ref "C6") (pin "2") (pinfunction "2_2") (pintype "passive"))
      (node (ref "C7") (pin "2") (pinfunction "2_2") (pintype "passive"))
      (node (ref "C8") (pin "2") (pinfunction "2_2") (pintype "passive"))
      (node (ref "C9") (pin "2") (pinfunction "2_2") (pintype "passive"))
      (node (ref "D1") (pin "C") (pinfunction "K_C") (pintype "passive"))
      (node (ref "D2") (pin "C") (pinfunction "K_C") (pintype "passive"))
      (node (ref "D3") (pin "C") (pinfunction "K_C") (pintype "passive"))
      (node (ref "D4") (pin "C") (pinfunction "K_C") (pintype "passive"))
      (node (ref "D5") (pin "A") (pinfunction "A_A") (pintype "passive"))
      (node (ref "D6") (pin "A") (pinfunction "A_A") (pintype "passive"))
      (node (ref "D7") (pin "A") (pinfunction "A_A") (pintype "passive"))
      (node (ref "D8") (pin "3") (pinfunction "K_3_3") (pintype "bidirectional"))
      (node (ref "D9") (pin "3") (pinfunction "K_3_3") (pintype "bidirectional"))
      (node (ref "IC1") (pin "2") (pinfunction "GND_2") (pintype "bidirectional"))
      (node (ref "IC2") (pin "2") (pinfunction "GND_2") (pintype "bidirectional"))
      (node (ref "IC3") (pin "14") (pinfunction "MODE_14") (pintype "input"))
      (node (ref "IC3") (pin "17") (pinfunction "GND_17") (pintype "power_in"))
      (node (ref "IC3") (pin "2") (pinfunction "RT_2") (pintype "input"))
      (node (ref "IC4") (pin "10") (pinfunction "GND_(EP)_2_10") (pintype "power_in"))
      (node (ref "IC4") (pin "5") (pinfunction "GND_5") (pintype "power_in"))
      (node (ref "IC4") (pin "9") (pinfunction "GND_(EP)_1_9") (pintype "power_in"))
      (node (ref "J1") (pin "5") (pinfunction "5_5") (pintype "bidirectional"))
      (node (ref "J1") (pin "MP1") (pinfunction "MP1_MP1") (pintype "bidirectional"))
      (node (ref "J1") (pin "MP2") (pinfunction "MP2_MP2") (pintype "bidirectional"))
      (node (ref "J2") (pin "2") (pinfunction "2_2") (pintype "bidirectional"))
      (node (ref "J2") (pin "4") (pinfunction "4_4") (pintype "bidirectional"))
      (node (ref "J2") (pin "7") (pinfunction "7_7") (pintype "bidirectional"))
      (node (ref "J2") (pin "9") (pinfunction "9_9") (pintype "bidirectional"))
      (node (ref "J3") (pin "5") (pinfunction "5_5") (pintype "bidirectional"))
      (node (ref "J3") (pin "MP1") (pinfunction "MP1_MP1") (pintype "bidirectional"))
      (node (ref "J3") (pin "MP2") (pinfunction "MP2_MP2") (pintype "bidirectional"))
      (node (ref "K1") (pin "12") (pinfunction "-_12") (pintype "bidirectional"))
      (node (ref "K2") (pin "12") (pinfunction "-_12") (pintype "bidirectional"))
      (node (ref "K3") (pin "12") (pinfunction "-_12") (pintype "bidirectional"))
      (node (ref "Q3") (pin "3") (pinfunction "3E_3") (pintype "bidirectional"))
      (node (ref "Q5") (pin "2") (pinfunction "S_2") (pintype "passive"))
      (node (ref "Q6") (pin "2") (pinfunction "S_2") (pintype "passive"))
      (node (ref "Q7") (pin "3") (pinfunction "3E_3") (pintype "bidirectional"))
      (node (ref "R12") (pin "2") (pinfunction "2_2") (pintype "passive"))
      (node (ref "R13") (pin "1") (pinfunction "1_1") (pintype "passive"))
      (node (ref "R14") (pin "2") (pinfunction "2_2") (pintype "passive"))
      (node (ref "R15") (pin "2") (pinfunction "2_2") (pintype "passive"))
      (node (ref "R16") (pin "2") (pinfunction "2_2") (pintype "passive"))
      (node (ref "R29") (pin "1") (pinfunction "1_1") (pintype "passive"))
      (node (ref "R3") (pin "2") (pinfunction "2_2") (pintype "passive"))
      (node (ref "R32") (pin "1") (pinfunction "1_1") (pintype "passive"))
      (node (ref "R33") (pin "1") (pinfunction "1_1") (pintype "passive"))
      (node (ref "R42") (pin "2") (pinfunction "2_2") (pintype "passive"))
      (node (ref "R43") (pin "2") (pinfunction "2_2") (pintype "passive"))
      (node (ref "R52") (pin "1") (pinfunction "1_1") (pintype "passive"))
      (node (ref "R53") (pin "1") (pinfunction "1_1") (pintype "passive"))
      (node (ref "R54") (pin "2") (pinfunction "2_2") (pintype "passive"))
      (node (ref "R62") (pin "2") (pinfunction "2_2") (pintype "passive"))
      (node (ref "R63") (pin "2") (pinfunction "2_2") (pintype "passive"))
      (node (ref "R68") (pin "2") (pinfunction "2_2") (pintype "passive"))
      (node (ref "R71") (pin "1") (pinfunction "1_1") (pintype "passive"))
      (node (ref "S1") (pin "1") (pinfunction "1_1") (pintype "bidirectional"))
      (node (ref "S1") (pin "2") (pinfunction "2_2") (pintype "bidirectional"))
      (node (ref "S3") (pin "1") (pinfunction "1_1") (pintype "bidirectional"))
      (node (ref "S3") (pin "2") (pinfunction "2_2") (pintype "bidirectional"))
      (node (ref "SWD1") (pin "5") (pinfunction "GND_5") (pintype "passive"))
      (node (ref "SWD2") (pin "5") (pinfunction "GND_5") (pintype "passive"))
      (node (ref "U1") (pin "16") (pinfunction "VSS_2_16") (pintype "power_in"))
      (node (ref "U1") (pin "32") (pinfunction "VSS_32") (pintype "power_in"))
      (node (ref "U3") (pin "1") (pinfunction "GND_1") (pintype "passive"))
      (node (ref "U6") (pin "16") (pinfunction "VSS_2_16") (pintype "power_in"))
      (node (ref "U6") (pin "32") (pinfunction "VSS_32") (pintype "power_in"))
    )
    (net (code "41") (name "NRST_TCU") (class "Default")
      (node (ref "C4") (pin "1") (pinfunction "1_1") (pintype "passive"))
      (node (ref "J1") (pin "3") (pinfunction "3_3") (pintype "bidirectional"))
      (node (ref "R2") (pin "1") (pinfunction "1_1") (pintype "passive"))
      (node (ref "S3") (pin "3") (pinfunction "3_3") (pintype "bidirectional"))
      (node (ref "S3") (pin "4") (pinfunction "4_4") (pintype "bidirectional"))
      (node (ref "SWD1") (pin "3") (pinfunction "~{RST}_3") (pintype "passive"))
      (node (ref "U1") (pin "4") (pinfunction "NRST_4") (pintype "bidirectional"))
    )
    (net (code "42") (name "NRST_UCU") (class "Default")
      (node (ref "C36") (pin "1") (pinfunction "1_1") (pintype "passive"))
      (node (ref "J3") (pin "3") (pinfunction "3_3") (pintype "bidirectional"))
      (node (ref "R69") (pin "1") (pinfunction "1_1") (pintype "passive"))
      (node (ref "S1") (pin "3") (pinfunction "3_3") (pintype "bidirectional"))
      (node (ref "S1") (pin "4") (pinfunction "4_4") (pintype "bidirectional"))
      (node (ref "SWD2") (pin "3") (pinfunction "~{RST}_3") (pintype "passive"))
      (node (ref "U6") (pin "4") (pinfunction "NRST_4") (pintype "bidirectional"))
    )
    (net (code "43") (name "Net-(D1-PadA)") (class "Default")
      (node (ref "D1") (pin "A") (pinfunction "A_A") (pintype "passive"))
      (node (ref "R6") (pin "1") (pinfunction "1_1") (pintype "passive"))
    )
    (net (code "44") (name "Net-(D2-PadA)") (class "Default")
      (node (ref "D2") (pin "A") (pinfunction "A_A") (pintype "passive"))
      (node (ref "R7") (pin "1") (pinfunction "1_1") (pintype "passive"))
    )
    (net (code "45") (name "Net-(D3-PadA)") (class "Default")
      (node (ref "D3") (pin "A") (pinfunction "A_A") (pintype "passive"))
      (node (ref "R8") (pin "1") (pinfunction "1_1") (pintype "passive"))
    )
    (net (code "46") (name "Net-(D4-PadA)") (class "Default")
      (node (ref "D4") (pin "A") (pinfunction "A_A") (pintype "passive"))
      (node (ref "R9") (pin "1") (pinfunction "1_1") (pintype "passive"))
    )
    (net (code "47") (name "Net-(IC1-RS)") (class "Default")
      (node (ref "IC1") (pin "8") (pinfunction "RS_8") (pintype "bidirectional"))
      (node (ref "R51") (pin "1") (pinfunction "1_1") (pintype "passive"))
      (node (ref "R52") (pin "2") (pinfunction "2_2") (pintype "passive"))
    )
    (net (code "48") (name "Net-(IC2-RS)") (class "Default")
      (node (ref "IC2") (pin "8") (pinfunction "RS_8") (pintype "bidirectional"))
      (node (ref "R13") (pin "2") (pinfunction "2_2") (pintype "passive"))
      (node (ref "R5") (pin "1") (pinfunction "1_1") (pintype "passive"))
    )
    (net (code "49") (name "Net-(IC3-ADJ+)") (class "Default")
      (node (ref "IC3") (pin "15") (pinfunction "ADJ+_15") (pintype "input"))
      (node (ref "R4") (pin "1") (pinfunction "1_1") (pintype "passive"))
      (node (ref "R53") (pin "2") (pinfunction "2_2") (pintype "passive"))
    )
    (net (code "50") (name "Net-(IC3-ADJ-)") (class "Default")
      (node (ref "IC3") (pin "4") (pinfunction "ADJ-_4") (pintype "input"))
      (node (ref "R54") (pin "1") (pinfunction "1_1") (pintype "passive"))
      (node (ref "R55") (pin "2") (pinfunction "2_2") (pintype "passive"))
    )
    (net (code "51") (name "Net-(IC3-BYP+)") (class "Default")
      (node (ref "C30") (pin "1") (pinfunction "1_1") (pintype "passive"))
      (node (ref "IC3") (pin "16") (pinfunction "BYP+_16") (pintype "bidirectional"))
    )
    (net (code "52") (name "Net-(IC3-BYP-)") (class "Default")
      (node (ref "C29") (pin "1") (pinfunction "1_1") (pintype "passive"))
      (node (ref "IC3") (pin "3") (pinfunction "BYP-_3") (pintype "bidirectional"))
    )
    (net (code "53") (name "Net-(IC3-C+)") (class "Default")
      (node (ref "C25") (pin "2") (pinfunction "2_2") (pintype "passive"))
      (node (ref "IC3") (pin "10") (pinfunction "C+_10") (pintype "bidirectional"))
    )
    (net (code "54") (name "Net-(IC3-C-)") (class "Default")
      (node (ref "C25") (pin "1") (pinfunction "1_1") (pintype "passive"))
      (node (ref "IC3") (pin "7") (pinfunction "C-_7") (pintype "bidirectional"))
    )
    (net (code "55") (name "Net-(IC3-VOUT)") (class "Default")
      (node (ref "C26") (pin "2") (pinfunction "2_2") (pintype "passive"))
      (node (ref "IC3") (pin "6") (pinfunction "VOUT_6") (pintype "output"))
    )
    (net (code "56") (name "Net-(IC4-FB)") (class "Default")
      (node (ref "IC4") (pin "2") (pinfunction "FB_2") (pintype "bidirectional"))
      (node (ref "R11") (pin "2") (pinfunction "2_2") (pintype "passive"))
      (node (ref "R12") (pin "1") (pinfunction "1_1") (pintype "passive"))
    )
    (net (code "57") (name "Net-(IC4-PG)") (class "Default")
      (node (ref "IC4") (pin "3") (pinfunction "PG_3") (pintype "bidirectional"))
      (node (ref "R10") (pin "2") (pinfunction "2_2") (pintype "passive"))
    )
    (net (code "58") (name "Net-(IC4-SS)") (class "Default")
      (node (ref "C18") (pin "1") (pinfunction "1_1") (pintype "passive"))
      (node (ref "IC4") (pin "1") (pinfunction "SS_1") (pintype "bidirectional"))
    )
    (net (code "59") (name "Net-(K1-COM_1)") (class "Default")
      (node (ref "K1") (pin "4") (pinfunction "COM_1_4") (pintype "bidirectional"))
      (node (ref "R46") (pin "2") (pinfunction "2_2") (pintype "passive"))
    )
    (net (code "60") (name "Net-(K1-COM_2)") (class "Default")
      (node (ref "K1") (pin "9") (pinfunction "COM_2_9") (pintype "bidirectional"))
      (node (ref "R47") (pin "1") (pinfunction "1_1") (pintype "passive"))
    )
    (net (code "61") (name "Net-(K2-COM_1)") (class "Default")
      (node (ref "K2") (pin "4") (pinfunction "COM_1_4") (pintype "bidirectional"))
      (node (ref "R48") (pin "2") (pinfunction "2_2") (pintype "passive"))
    )
    (net (code "62") (name "Net-(K2-COM_2)") (class "Default")
      (node (ref "K2") (pin "9") (pinfunction "COM_2_9") (pintype "bidirectional"))
      (node (ref "R49") (pin "2") (pinfunction "2_2") (pintype "passive"))
    )
    (net (code "63") (name "Net-(K3-COM_1)") (class "Default")
      (node (ref "K3") (pin "4") (pinfunction "COM_1_4") (pintype "bidirectional"))
      (node (ref "R50") (pin "2") (pinfunction "2_2") (pintype "passive"))
    )
    (net (code "64") (name "Net-(K4--)") (class "Default")
      (node (ref "D10") (pin "A") (pinfunction "A_A") (pintype "passive"))
      (node (ref "K4") (pin "12") (pinfunction "-_12") (pintype "bidirectional"))
      (node (ref "Q4") (pin "3") (pinfunction "D_3") (pintype "passive"))
    )
    (net (code "65") (name "Net-(K4-NO_1)") (class "Default")
      (node (ref "K4") (pin "5") (pinfunction "NO_1_5") (pintype "bidirectional"))
      (node (ref "Q6") (pin "3") (pinfunction "D_3") (pintype "passive"))
    )
    (net (code "66") (name "Net-(Q2-D)") (class "Default")
      (node (ref "Q2") (pin "3") (pinfunction "D_3") (pintype "passive"))
      (node (ref "Q7") (pin "2") (pinfunction "2C_2") (pintype "bidirectional"))
    )
    (net (code "67") (name "Net-(Q3-2C)") (class "Default")
      (node (ref "Q3") (pin "2") (pinfunction "2C_2") (pintype "bidirectional"))
      (node (ref "R56") (pin "2") (pinfunction "2_2") (pintype "passive"))
    )
    (net (code "68") (name "Net-(Q3-4C)") (class "Default")
      (node (ref "C31") (pin "1") (pinfunction "1_1") (pintype "passive"))
      (node (ref "C32") (pin "1") (pinfunction "1_1") (pintype "passive"))
      (node (ref "Q3") (pin "4") (pinfunction "4C_4") (pintype "bidirectional"))
      (node (ref "Q4") (pin "1") (pinfunction "G_1") (pintype "passive"))
      (node (ref "R61") (pin "2") (pinfunction "2_2") (pintype "passive"))
    )
    (net (code "69") (name "Net-(Q4-S)") (class "Default")
      (node (ref "Q4") (pin "2") (pinfunction "S_2") (pintype "passive"))
      (node (ref "Q5") (pin "3") (pinfunction "D_3") (pintype "passive"))
    )
    (net (code "70") (name "Net-(Q7-1A)") (class "Default")
      (node (ref "Q7") (pin "1") (pinfunction "1A_1") (pintype "bidirectional"))
      (node (ref "R66") (pin "2") (pinfunction "2_2") (pintype "passive"))
    )
    (net (code "71") (name "Net-(U1-BOOT0)") (class "Default")
      (node (ref "R3") (pin "1") (pinfunction "1_1") (pintype "passive"))
      (node (ref "U1") (pin "31") (pinfunction "BOOT0_31") (pintype "input"))
    )
    (net (code "72") (name "Net-(U1-PA4)") (class "Default")
      (node (ref "U1") (pin "10") (pinfunction "PA4_10") (pintype "bidirectional"))
      (node (ref "U2") (pin "10") (pinfunction "3IN+_10") (pintype "input"))
    )
    (net (code "73") (name "Net-(U1-PA5)") (class "Default")
      (node (ref "U1") (pin "11") (pinfunction "PA5_11") (pintype "bidirectional"))
      (node (ref "U2") (pin "5") (pinfunction "2IN+_5") (pintype "input"))
    )
    (net (code "74") (name "Net-(U1-PA6)") (class "Default")
      (node (ref "U1") (pin "12") (pinfunction "PA6_12") (pintype "bidirectional"))
      (node (ref "U2") (pin "3") (pinfunction "1IN+_3") (pintype "input"))
    )
    (net (code "75") (name "Net-(U1-VDDA{slash}VREF+)") (class "Default")
      (node (ref "C2") (pin "1") (pinfunction "1_1") (pintype "passive"))
      (node (ref "R1") (pin "1") (pinfunction "1_1") (pintype "passive"))
      (node (ref "U1") (pin "5") (pinfunction "VDDA/VREF+_5") (pintype "power_in"))
    )
    (net (code "76") (name "Net-(U4-1IN+)") (class "Default")
      (node (ref "R22") (pin "1") (pinfunction "1_1") (pintype "passive"))
      (node (ref "R26") (pin "2") (pinfunction "2_2") (pintype "passive"))
      (node (ref "U4") (pin "3") (pinfunction "1IN+_3") (pintype "input"))
    )
    (net (code "77") (name "Net-(U4-1IN-)") (class "Default")
      (node (ref "R14") (pin "1") (pinfunction "1_1") (pintype "passive"))
      (node (ref "R18") (pin "2") (pinfunction "2_2") (pintype "passive"))
      (node (ref "U4") (pin "2") (pinfunction "1IN-_2") (pintype "input"))
    )
    (net (code "78") (name "Net-(U4-2IN+)") (class "Default")
      (node (ref "R23") (pin "1") (pinfunction "1_1") (pintype "passive"))
      (node (ref "R27") (pin "2") (pinfunction "2_2") (pintype "passive"))
      (node (ref "U4") (pin "5") (pinfunction "2IN+_5") (pintype "input"))
    )
    (net (code "79") (name "Net-(U4-2IN-)") (class "Default")
      (node (ref "R15") (pin "1") (pinfunction "1_1") (pintype "passive"))
      (node (ref "R19") (pin "2") (pinfunction "2_2") (pintype "passive"))
      (node (ref "U4") (pin "6") (pinfunction "2IN-_6") (pintype "input"))
    )
    (net (code "80") (name "Net-(U4-3IN+)") (class "Default")
      (node (ref "R31") (pin "2") (pinfunction "2_2") (pintype "passive"))
      (node (ref "R35") (pin "1") (pinfunction "1_1") (pintype "passive"))
      (node (ref "U4") (pin "10") (pinfunction "3IN+_10") (pintype "input"))
    )
    (net (code "81") (name "Net-(U4-3IN-)") (class "Default")
      (node (ref "R39") (pin "2") (pinfunction "2_2") (pintype "passive"))
      (node (ref "R43") (pin "1") (pinfunction "1_1") (pintype "passive"))
      (node (ref "U4") (pin "9") (pinfunction "3IN-_9") (pintype "input"))
    )
    (net (code "82") (name "Net-(U4-4IN+)") (class "Default")
      (node (ref "R30") (pin "2") (pinfunction "2_2") (pintype "passive"))
      (node (ref "R34") (pin "1") (pinfunction "1_1") (pintype "passive"))
      (node (ref "U4") (pin "12") (pinfunction "4IN+_12") (pintype "input"))
    )
    (net (code "83") (name "Net-(U4-4IN-)") (class "Default")
      (node (ref "R38") (pin "2") (pinfunction "2_2") (pintype "passive"))
      (node (ref "R42") (pin "1") (pinfunction "1_1") (pintype "passive"))
      (node (ref "U4") (pin "13") (pinfunction "4IN-_13") (pintype "input"))
    )
    (net (code "84") (name "Net-(U5-1IN+)") (class "Default")
      (node (ref "R24") (pin "1") (pinfunction "1_1") (pintype "passive"))
      (node (ref "R28") (pin "2") (pinfunction "2_2") (pintype "passive"))
      (node (ref "U5") (pin "3") (pinfunction "1IN+_3") (pintype "input"))
    )
    (net (code "85") (name "Net-(U5-1IN-)") (class "Default")
      (node (ref "R16") (pin "1") (pinfunction "1_1") (pintype "passive"))
      (node (ref "R20") (pin "2") (pinfunction "2_2") (pintype "passive"))
      (node (ref "U5") (pin "2") (pinfunction "1IN-_2") (pintype "input"))
    )
    (net (code "86") (name "Net-(U5-2IN+)") (class "Default")
      (node (ref "R25") (pin "1") (pinfunction "1_1") (pintype "passive"))
      (node (ref "R29") (pin "2") (pinfunction "2_2") (pintype "passive"))
      (node (ref "U5") (pin "5") (pinfunction "2IN+_5") (pintype "input"))
    )
    (net (code "87") (name "Net-(U5-2IN-)") (class "Default")
      (node (ref "R17") (pin "1") (pinfunction "1_1") (pintype "passive"))
      (node (ref "R21") (pin "2") (pinfunction "2_2") (pintype "passive"))
      (node (ref "U5") (pin "6") (pinfunction "2IN-_6") (pintype "input"))
    )
    (net (code "88") (name "Net-(U5-3IN+)") (class "Default")
      (node (ref "R33") (pin "2") (pinfunction "2_2") (pintype "passive"))
      (node (ref "R37") (pin "1") (pinfunction "1_1") (pintype "passive"))
      (node (ref "U5") (pin "10") (pinfunction "3IN+_10") (pintype "input"))
    )
    (net (code "89") (name "Net-(U5-3IN-)") (class "Default")
      (node (ref "R41") (pin "2") (pinfunction "2_2") (pintype "passive"))
      (node (ref "R45") (pin "1") (pinfunction "1_1") (pintype "passive"))
      (node (ref "U5") (pin "9") (pinfunction "3IN-_9") (pintype "input"))
    )
    (net (code "90") (name "Net-(U5-4IN+)") (class "Default")
      (node (ref "R32") (pin "2") (pinfunction "2_2") (pintype "passive"))
      (node (ref "R36") (pin "1") (pinfunction "1_1") (pintype "passive"))
      (node (ref "U5") (pin "12") (pinfunction "4IN+_12") (pintype "input"))
    )
    (net (code "91") (name "Net-(U5-4IN-)") (class "Default")
      (node (ref "R40") (pin "2") (pinfunction "2_2") (pintype "passive"))
      (node (ref "R44") (pin "1") (pinfunction "1_1") (pintype "passive"))
      (node (ref "U5") (pin "13") (pinfunction "4IN-_13") (pintype "input"))
    )
    (net (code "92") (name "Net-(U6-BOOT0)") (class "Default")
      (node (ref "R68") (pin "1") (pinfunction "1_1") (pintype "passive"))
      (node (ref "U6") (pin "31") (pinfunction "BOOT0_31") (pintype "input"))
    )
    (net (code "93") (name "Net-(U6-VDDA{slash}VREF+)") (class "Default")
      (node (ref "C35") (pin "1") (pinfunction "1_1") (pintype "passive"))
      (node (ref "R64") (pin "1") (pinfunction "1_1") (pintype "passive"))
      (node (ref "U6") (pin "5") (pinfunction "VDDA/VREF+_5") (pintype "power_in"))
    )
    (net (code "94") (name "RPS1_GND") (class "Default")
      (node (ref "C12") (pin "1") (pinfunction "1_1") (pintype "passive"))
      (node (ref "FRONT_CONNECTOR") (pin "38") (pinfunction "38_38") (pintype "passive"))
      (node (ref "FRONT_CONNECTOR") (pin "49") (pinfunction "49_49") (pintype "passive"))
      (node (ref "R30") (pin "1") (pinfunction "1_1") (pintype "passive"))
      (node (ref "R45") (pin "2") (pinfunction "2_2") (pintype "passive"))
    )
    (net (code "95") (name "RPS1_IN") (class "Default")
      (node (ref "FRONT_CONNECTOR") (pin "37") (pinfunction "37_37") (pintype "passive"))
      (node (ref "K1") (pin "3") (pinfunction "NC_1_3") (pintype "bidirectional"))
      (node (ref "R37") (pin "2") (pinfunction "2_2") (pintype "passive"))
    )
    (net (code "96") (name "RPS1_OUT") (class "Default")
      (node (ref "C12") (pin "2") (pinfunction "2_2") (pintype "passive"))
      (node (ref "FRONT_CONNECTOR") (pin "50") (pinfunction "50_50") (pintype "passive"))
      (node (ref "R46") (pin "1") (pinfunction "1_1") (pintype "passive"))
    )
    (net (code "97") (name "RPS1_SIG_OUT") (class "Default")
      (node (ref "K1") (pin "5") (pinfunction "NO_1_5") (pintype "bidirectional"))
      (node (ref "R38") (pin "1") (pinfunction "1_1") (pintype "passive"))
      (node (ref "U4") (pin "14") (pinfunction "4OUT_14") (pintype "output"))
    )
    (net (code "98") (name "RPS1_VCC") (class "Default")
      (node (ref "FRONT_CONNECTOR") (pin "47") (pinfunction "47_47") (pintype "passive"))
      (node (ref "FRONT_CONNECTOR") (pin "48") (pinfunction "48_48") (pintype "passive"))
    )
    (net (code "99") (name "RPS2_GND") (class "Default")
      (node (ref "C13") (pin "1") (pinfunction "1_1") (pintype "passive"))
      (node (ref "FRONT_CONNECTOR") (pin "29") (pinfunction "29_29") (pintype "passive"))
      (node (ref "FRONT_CONNECTOR") (pin "30") (pinfunction "30_30") (pintype "passive"))
      (node (ref "R31") (pin "1") (pinfunction "1_1") (pintype "passive"))
    )
    (net (code "100") (name "RPS2_IN") (class "Default")
      (node (ref "FRONT_CONNECTOR") (pin "27") (pinfunction "27_27") (pintype "passive"))
      (node (ref "K1") (pin "10") (pinfunction "NC_2_10") (pintype "bidirectional"))
    )
    (net (code "101") (name "RPS2_OUT") (class "Default")
      (node (ref "C13") (pin "2") (pinfunction "2_2") (pintype "passive"))
      (node (ref "FRONT_CONNECTOR") (pin "40") (pinfunction "40_40") (pintype "passive"))
      (node (ref "R47") (pin "2") (pinfunction "2_2") (pintype "passive"))
    )
    (net (code "102") (name "RPS2_SIG_OUT") (class "Default")
      (node (ref "K1") (pin "8") (pinfunction "NO_2_8") (pintype "bidirectional"))
      (node (ref "R39") (pin "1") (pinfunction "1_1") (pintype "passive"))
      (node (ref "U4") (pin "8") (pinfunction "3OUT_8") (pintype "output"))
    )
    (net (code "103") (name "RPS2_VCC") (class "Default")
      (node (ref "FRONT_CONNECTOR") (pin "28") (pinfunction "28_28") (pintype "passive"))
      (node (ref "FRONT_CONNECTOR") (pin "39") (pinfunction "39_39") (pintype "passive"))
    )
    (net (code "104") (name "RPS_STM_ANOUT") (class "Default")
      (node (ref "R34") (pin "2") (pinfunction "2_2") (pintype "passive"))
      (node (ref "R35") (pin "2") (pinfunction "2_2") (pintype "passive"))
      (node (ref "U2") (pin "8") (pinfunction "3OUT_8") (pintype "output"))
      (node (ref "U2") (pin "9") (pinfunction "3IN-_9") (pintype "input"))
    )
    (net (code "105") (name "RPS_STM_IN") (class "Default")
      (node (ref "R41") (pin "1") (pinfunction "1_1") (pintype "passive"))
      (node (ref "U1") (pin "6") (pinfunction "PA0_6") (pintype "bidirectional"))
      (node (ref "U5") (pin "8") (pinfunction "3OUT_8") (pintype "output"))
    )
    (net (code "106") (name "RS_TCU") (class "Default")
      (node (ref "R51") (pin "2") (pinfunction "2_2") (pintype "passive"))
      (node (ref "U1") (pin "3") (pinfunction "PF1-OSC_OUT_3") (pintype "bidirectional"))
    )
    (net (code "107") (name "RS_UCU") (class "Default")
      (node (ref "R5") (pin "2") (pinfunction "2_2") (pintype "passive"))
      (node (ref "U6") (pin "3") (pinfunction "PF1-OSC_OUT_3") (pintype "bidirectional"))
    )
    (net (code "108") (name "RX_TCU") (class "Default")
      (node (ref "J1") (pin "7") (pinfunction "7_7") (pintype "bidirectional"))
      (node (ref "U1") (pin "25") (pinfunction "PA15_25") (pintype "bidirectional"))
    )
    (net (code "109") (name "RX_UCU") (class "Default")
      (node (ref "J3") (pin "7") (pinfunction "7_7") (pintype "bidirectional"))
      (node (ref "U6") (pin "25") (pinfunction "PA15_25") (pintype "bidirectional"))
    )
    (net (code "110") (name "R_TCU") (class "Default")
      (node (ref "IC1") (pin "4") (pinfunction "R_4") (pintype "bidirectional"))
      (node (ref "U1") (pin "21") (pinfunction "PA11_21") (pintype "bidirectional"))
    )
    (net (code "111") (name "R_UCU") (class "Default")
      (node (ref "IC2") (pin "4") (pinfunction "R_4") (pintype "bidirectional"))
      (node (ref "U6") (pin "21") (pinfunction "PA11_21") (pintype "bidirectional"))
    )
    (net (code "112") (name "SPEED_SENS_12V") (class "Default")
      (node (ref "FRONT_CONNECTOR") (pin "18") (pinfunction "18_18") (pintype "passive"))
      (node (ref "FRONT_CONNECTOR") (pin "8") (pinfunction "8_8") (pintype "passive"))
      (node (ref "R66") (pin "1") (pinfunction "1_1") (pintype "passive"))
    )
    (net (code "113") (name "SPEED_SENS_GND") (class "Default")
      (node (ref "FRONT_CONNECTOR") (pin "19") (pinfunction "19_19") (pintype "passive"))
      (node (ref "FRONT_CONNECTOR") (pin "9") (pinfunction "9_9") (pintype "passive"))
      (node (ref "Q2") (pin "2") (pinfunction "S_2") (pintype "passive"))
      (node (ref "R67") (pin "1") (pinfunction "1_1") (pintype "passive"))
    )
    (net (code "114") (name "SPEED_SENS_IN") (class "Default")
      (node (ref "Q7") (pin "4") (pinfunction "4C_4") (pintype "bidirectional"))
      (node (ref "R65") (pin "1") (pinfunction "1_1") (pintype "passive"))
      (node (ref "U6") (pin "15") (pinfunction "PB1_15") (pintype "bidirectional"))
    )
    (net (code "115") (name "SPEED_SENS_SIG") (class "Default")
      (node (ref "FRONT_CONNECTOR") (pin "10") (pinfunction "10_10") (pintype "passive"))
      (node (ref "FRONT_CONNECTOR") (pin "20") (pinfunction "20_20") (pintype "passive"))
      (node (ref "Q2") (pin "1") (pinfunction "G_1") (pintype "passive"))
      (node (ref "R67") (pin "2") (pinfunction "2_2") (pintype "passive"))
    )
    (net (code "116") (name "STM_12_INDIC") (class "Default")
      (node (ref "K3") (pin "9") (pinfunction "COM_2_9") (pintype "bidirectional"))
      (node (ref "R70") (pin "1") (pinfunction "1_1") (pintype "passive"))
      (node (ref "R71") (pin "2") (pinfunction "2_2") (pintype "passive"))
      (node (ref "U1") (pin "14") (pinfunction "PB0_14") (pintype "bidirectional"))
      (node (ref "U6") (pin "14") (pinfunction "PB0_14") (pintype "bidirectional"))
    )
    (net (code "117") (name "SWDCLK_TCU") (class "Default")
      (node (ref "J1") (pin "4") (pinfunction "4_4") (pintype "bidirectional"))
      (node (ref "SWD1") (pin "4") (pinfunction "SWDCLK_4") (pintype "passive"))
      (node (ref "U1") (pin "24") (pinfunction "PA14_24") (pintype "bidirectional"))
    )
    (net (code "118") (name "SWDCLK_UCU") (class "Default")
      (node (ref "J3") (pin "4") (pinfunction "4_4") (pintype "bidirectional"))
      (node (ref "SWD2") (pin "4") (pinfunction "SWDCLK_4") (pintype "passive"))
      (node (ref "U6") (pin "24") (pinfunction "PA14_24") (pintype "bidirectional"))
    )
    (net (code "119") (name "SWDIO_TCU") (class "Default")
      (node (ref "J1") (pin "2") (pinfunction "2_2") (pintype "bidirectional"))
      (node (ref "SWD1") (pin "2") (pinfunction "SWDIO_2") (pintype "passive"))
      (node (ref "U1") (pin "23") (pinfunction "PA13_23") (pintype "bidirectional"))
    )
    (net (code "120") (name "SWDIO_UCU") (class "Default")
      (node (ref "J3") (pin "2") (pinfunction "2_2") (pintype "bidirectional"))
      (node (ref "SWD2") (pin "2") (pinfunction "SWDIO_2") (pintype "passive"))
      (node (ref "U6") (pin "23") (pinfunction "PA13_23") (pintype "bidirectional"))
    )
    (net (code "121") (name "SWO_TCU") (class "Default")
      (node (ref "J1") (pin "6") (pinfunction "6_6") (pintype "bidirectional"))
      (node (ref "SWD1") (pin "6") (pinfunction "SWO_6") (pintype "passive"))
      (node (ref "U1") (pin "26") (pinfunction "PB3_26") (pintype "bidirectional"))
    )
    (net (code "122") (name "SWO_UCU") (class "Default")
      (node (ref "J3") (pin "6") (pinfunction "6_6") (pintype "bidirectional"))
      (node (ref "SWD2") (pin "6") (pinfunction "SWO_6") (pintype "passive"))
      (node (ref "U6") (pin "26") (pinfunction "PB3_26") (pintype "bidirectional"))
    )
    (net (code "123") (name "TX_TCU") (class "Default")
      (node (ref "J1") (pin "8") (pinfunction "8_8") (pintype "bidirectional"))
      (node (ref "U1") (pin "8") (pinfunction "PA2_8") (pintype "bidirectional"))
    )
    (net (code "124") (name "TX_UCU") (class "Default")
      (node (ref "J3") (pin "8") (pinfunction "8_8") (pintype "bidirectional"))
      (node (ref "U6") (pin "8") (pinfunction "PA2_8") (pintype "bidirectional"))
    )
    (net (code "125") (name "unconnected-(AC1-NC_1-Pad8)") (class "Default")
      (node (ref "AC1") (pin "8") (pinfunction "NC_1_8") (pintype "bidirectional"))
    )
    (net (code "126") (name "unconnected-(AC1-NC_2-Pad9)") (class "Default")
      (node (ref "AC1") (pin "9") (pinfunction "NC_2_9") (pintype "bidirectional"))
    )
    (net (code "127") (name "unconnected-(AC1-NC_3-Pad10)") (class "Default")
      (node (ref "AC1") (pin "10") (pinfunction "NC_3_10") (pintype "bidirectional"))
    )
    (net (code "128") (name "unconnected-(AC1-NC_4-Pad11)") (class "Default")
      (node (ref "AC1") (pin "11") (pinfunction "NC_4_11") (pintype "bidirectional"))
    )
    (net (code "129") (name "unconnected-(AC1-NC_5-Pad12)") (class "Default")
      (node (ref "AC1") (pin "12") (pinfunction "NC_5_12") (pintype "bidirectional"))
    )
    (net (code "130") (name "unconnected-(AC1-NC_6-Pad13)") (class "Default")
      (node (ref "AC1") (pin "13") (pinfunction "NC_6_13") (pintype "bidirectional"))
    )
    (net (code "131") (name "unconnected-(AC1-RES_1-Pad1)") (class "Default")
      (node (ref "AC1") (pin "1") (pinfunction "RES_1_1") (pintype "bidirectional"))
    )
    (net (code "132") (name "unconnected-(AC1-RES_2-Pad3)") (class "Default")
      (node (ref "AC1") (pin "3") (pinfunction "RES_2_3") (pintype "bidirectional"))
    )
    (net (code "133") (name "unconnected-(FRONT_CONNECTOR-Pad1)") (class "Default")
      (node (ref "FRONT_CONNECTOR") (pin "1") (pinfunction "1_1") (pintype "passive"))
    )
    (net (code "134") (name "unconnected-(FRONT_CONNECTOR-Pad5)") (class "Default")
      (node (ref "FRONT_CONNECTOR") (pin "5") (pinfunction "5_5") (pintype "passive"))
    )
    (net (code "135") (name "unconnected-(FRONT_CONNECTOR-Pad15)") (class "Default")
      (node (ref "FRONT_CONNECTOR") (pin "15") (pinfunction "15_15") (pintype "passive"))
    )
    (net (code "136") (name "unconnected-(FRONT_CONNECTOR-Pad25)") (class "Default")
      (node (ref "FRONT_CONNECTOR") (pin "25") (pinfunction "25_25") (pintype "passive"))
    )
    (net (code "137") (name "unconnected-(FRONT_CONNECTOR-Pad26)") (class "Default")
      (node (ref "FRONT_CONNECTOR") (pin "26") (pinfunction "26_26") (pintype "passive"))
    )
    (net (code "138") (name "unconnected-(FRONT_CONNECTOR-Pad35)") (class "Default")
      (node (ref "FRONT_CONNECTOR") (pin "35") (pinfunction "35_35") (pintype "passive"))
    )
    (net (code "139") (name "unconnected-(FRONT_CONNECTOR-Pad36)") (class "Default")
      (node (ref "FRONT_CONNECTOR") (pin "36") (pinfunction "36_36") (pintype "passive"))
    )
    (net (code "140") (name "unconnected-(FRONT_CONNECTOR-Pad44)") (class "Default")
      (node (ref "FRONT_CONNECTOR") (pin "44") (pinfunction "44_44") (pintype "passive"))
    )
    (net (code "141") (name "unconnected-(FRONT_CONNECTOR-Pad45)") (class "Default")
      (node (ref "FRONT_CONNECTOR") (pin "45") (pinfunction "45_45") (pintype "passive"))
    )
    (net (code "142") (name "unconnected-(FRONT_CONNECTOR-Pad46)") (class "Default")
      (node (ref "FRONT_CONNECTOR") (pin "46") (pinfunction "46_46") (pintype "passive"))
    )
    (net (code "143") (name "unconnected-(H1-Pad1)") (class "Default")
      (node (ref "H1") (pin "1") (pinfunction "1_1") (pintype "bidirectional"))
    )
    (net (code "144") (name "unconnected-(IC1-VREF-Pad5)") (class "Default")
      (node (ref "IC1") (pin "5") (pinfunction "VREF_5") (pintype "bidirectional"))
    )
    (net (code "145") (name "unconnected-(IC2-VREF-Pad5)") (class "Default")
      (node (ref "IC2") (pin "5") (pinfunction "VREF_5") (pintype "bidirectional"))
    )
    (net (code "146") (name "unconnected-(IC3-NC_1-Pad8)") (class "Default")
      (node (ref "IC3") (pin "8") (pinfunction "NC_1_8") (pintype "bidirectional"))
    )
    (net (code "147") (name "unconnected-(IC3-NC_2-Pad9)") (class "Default")
      (node (ref "IC3") (pin "9") (pinfunction "NC_2_9") (pintype "bidirectional"))
    )
    (net (code "148") (name "unconnected-(K3-NC_2-Pad10)") (class "Default")
      (node (ref "K3") (pin "10") (pinfunction "NC_2_10") (pintype "bidirectional"))
    )
    (net (code "149") (name "unconnected-(U1-PA7-Pad13)") (class "Default")
      (node (ref "U1") (pin "13") (pinfunction "PA7_13") (pintype "bidirectional"))
    )
    (net (code "150") (name "unconnected-(U1-PA8-Pad18)") (class "Default")
      (node (ref "U1") (pin "18") (pinfunction "PA8_18") (pintype "bidirectional"))
    )
    (net (code "151") (name "unconnected-(U1-PA9-Pad19)") (class "Default")
      (node (ref "U1") (pin "19") (pinfunction "PA9_19") (pintype "bidirectional"))
    )
    (net (code "152") (name "unconnected-(U1-PA10-Pad20)") (class "Default")
      (node (ref "U1") (pin "20") (pinfunction "PA10_20") (pintype "bidirectional"))
    )
    (net (code "153") (name "unconnected-(U1-PB1-Pad15)") (class "Default")
      (node (ref "U1") (pin "15") (pinfunction "PB1_15") (pintype "bidirectional"))
    )
    (net (code "154") (name "unconnected-(U1-PB4-Pad27)") (class "Default")
      (node (ref "U1") (pin "27") (pinfunction "PB4_27") (pintype "bidirectional"))
    )
    (net (code "155") (name "unconnected-(U1-PB5-Pad28)") (class "Default")
      (node (ref "U1") (pin "28") (pinfunction "PB5_28") (pintype "bidirectional"))
    )
    (net (code "156") (name "unconnected-(U1-PB6-Pad29)") (class "Default")
      (node (ref "U1") (pin "29") (pinfunction "PB6_29") (pintype "bidirectional"))
    )
    (net (code "157") (name "unconnected-(U1-PB7-Pad30)") (class "Default")
      (node (ref "U1") (pin "30") (pinfunction "PB7_30") (pintype "bidirectional"))
    )
    (net (code "158") (name "unconnected-(U1-PF0-OSC_IN-Pad2)") (class "Default")
      (node (ref "U1") (pin "2") (pinfunction "PF0-OSC_IN_2") (pintype "bidirectional"))
    )
    (net (code "159") (name "unconnected-(U2-4IN+-Pad12)") (class "Default")
      (node (ref "U2") (pin "12") (pinfunction "4IN+_12") (pintype "input"))
    )
    (net (code "160") (name "unconnected-(U2-4IN--Pad13)") (class "Default")
      (node (ref "U2") (pin "13") (pinfunction "4IN-_13") (pintype "input"))
    )
    (net (code "161") (name "unconnected-(U2-4OUT-Pad14)") (class "Default")
      (node (ref "U2") (pin "14") (pinfunction "4OUT_14") (pintype "output"))
    )
    (net (code "162") (name "unconnected-(U6-PA5-Pad11)") (class "Default")
      (node (ref "U6") (pin "11") (pinfunction "PA5_11") (pintype "bidirectional"))
    )
    (net (code "163") (name "unconnected-(U6-PA6-Pad12)") (class "Default")
      (node (ref "U6") (pin "12") (pinfunction "PA6_12") (pintype "bidirectional"))
    )
    (net (code "164") (name "unconnected-(U6-PA7-Pad13)") (class "Default")
      (node (ref "U6") (pin "13") (pinfunction "PA7_13") (pintype "bidirectional"))
    )
    (net (code "165") (name "unconnected-(U6-PA9-Pad19)") (class "Default")
      (node (ref "U6") (pin "19") (pinfunction "PA9_19") (pintype "bidirectional"))
    )
    (net (code "166") (name "unconnected-(U6-PA10-Pad20)") (class "Default")
      (node (ref "U6") (pin "20") (pinfunction "PA10_20") (pintype "bidirectional"))
    )
    (net (code "167") (name "unconnected-(U6-PB5-Pad28)") (class "Default")
      (node (ref "U6") (pin "28") (pinfunction "PB5_28") (pintype "bidirectional"))
    )
    (net (code "168") (name "unconnected-(U6-PB6-Pad29)") (class "Default")
      (node (ref "U6") (pin "29") (pinfunction "PB6_29") (pintype "bidirectional"))
    )
    (net (code "169") (name "unconnected-(U6-PB7-Pad30)") (class "Default")
      (node (ref "U6") (pin "30") (pinfunction "PB7_30") (pintype "bidirectional"))
    )
    (net (code "170") (name "unconnected-(U6-PF0-OSC_IN-Pad2)") (class "Default")
      (node (ref "U6") (pin "2") (pinfunction "PF0-OSC_IN_2") (pintype "bidirectional"))
    )
  )
)
